# FM375_TEST_BOARD.net
KiCad netlist of a schematic drawn in Altium Designer
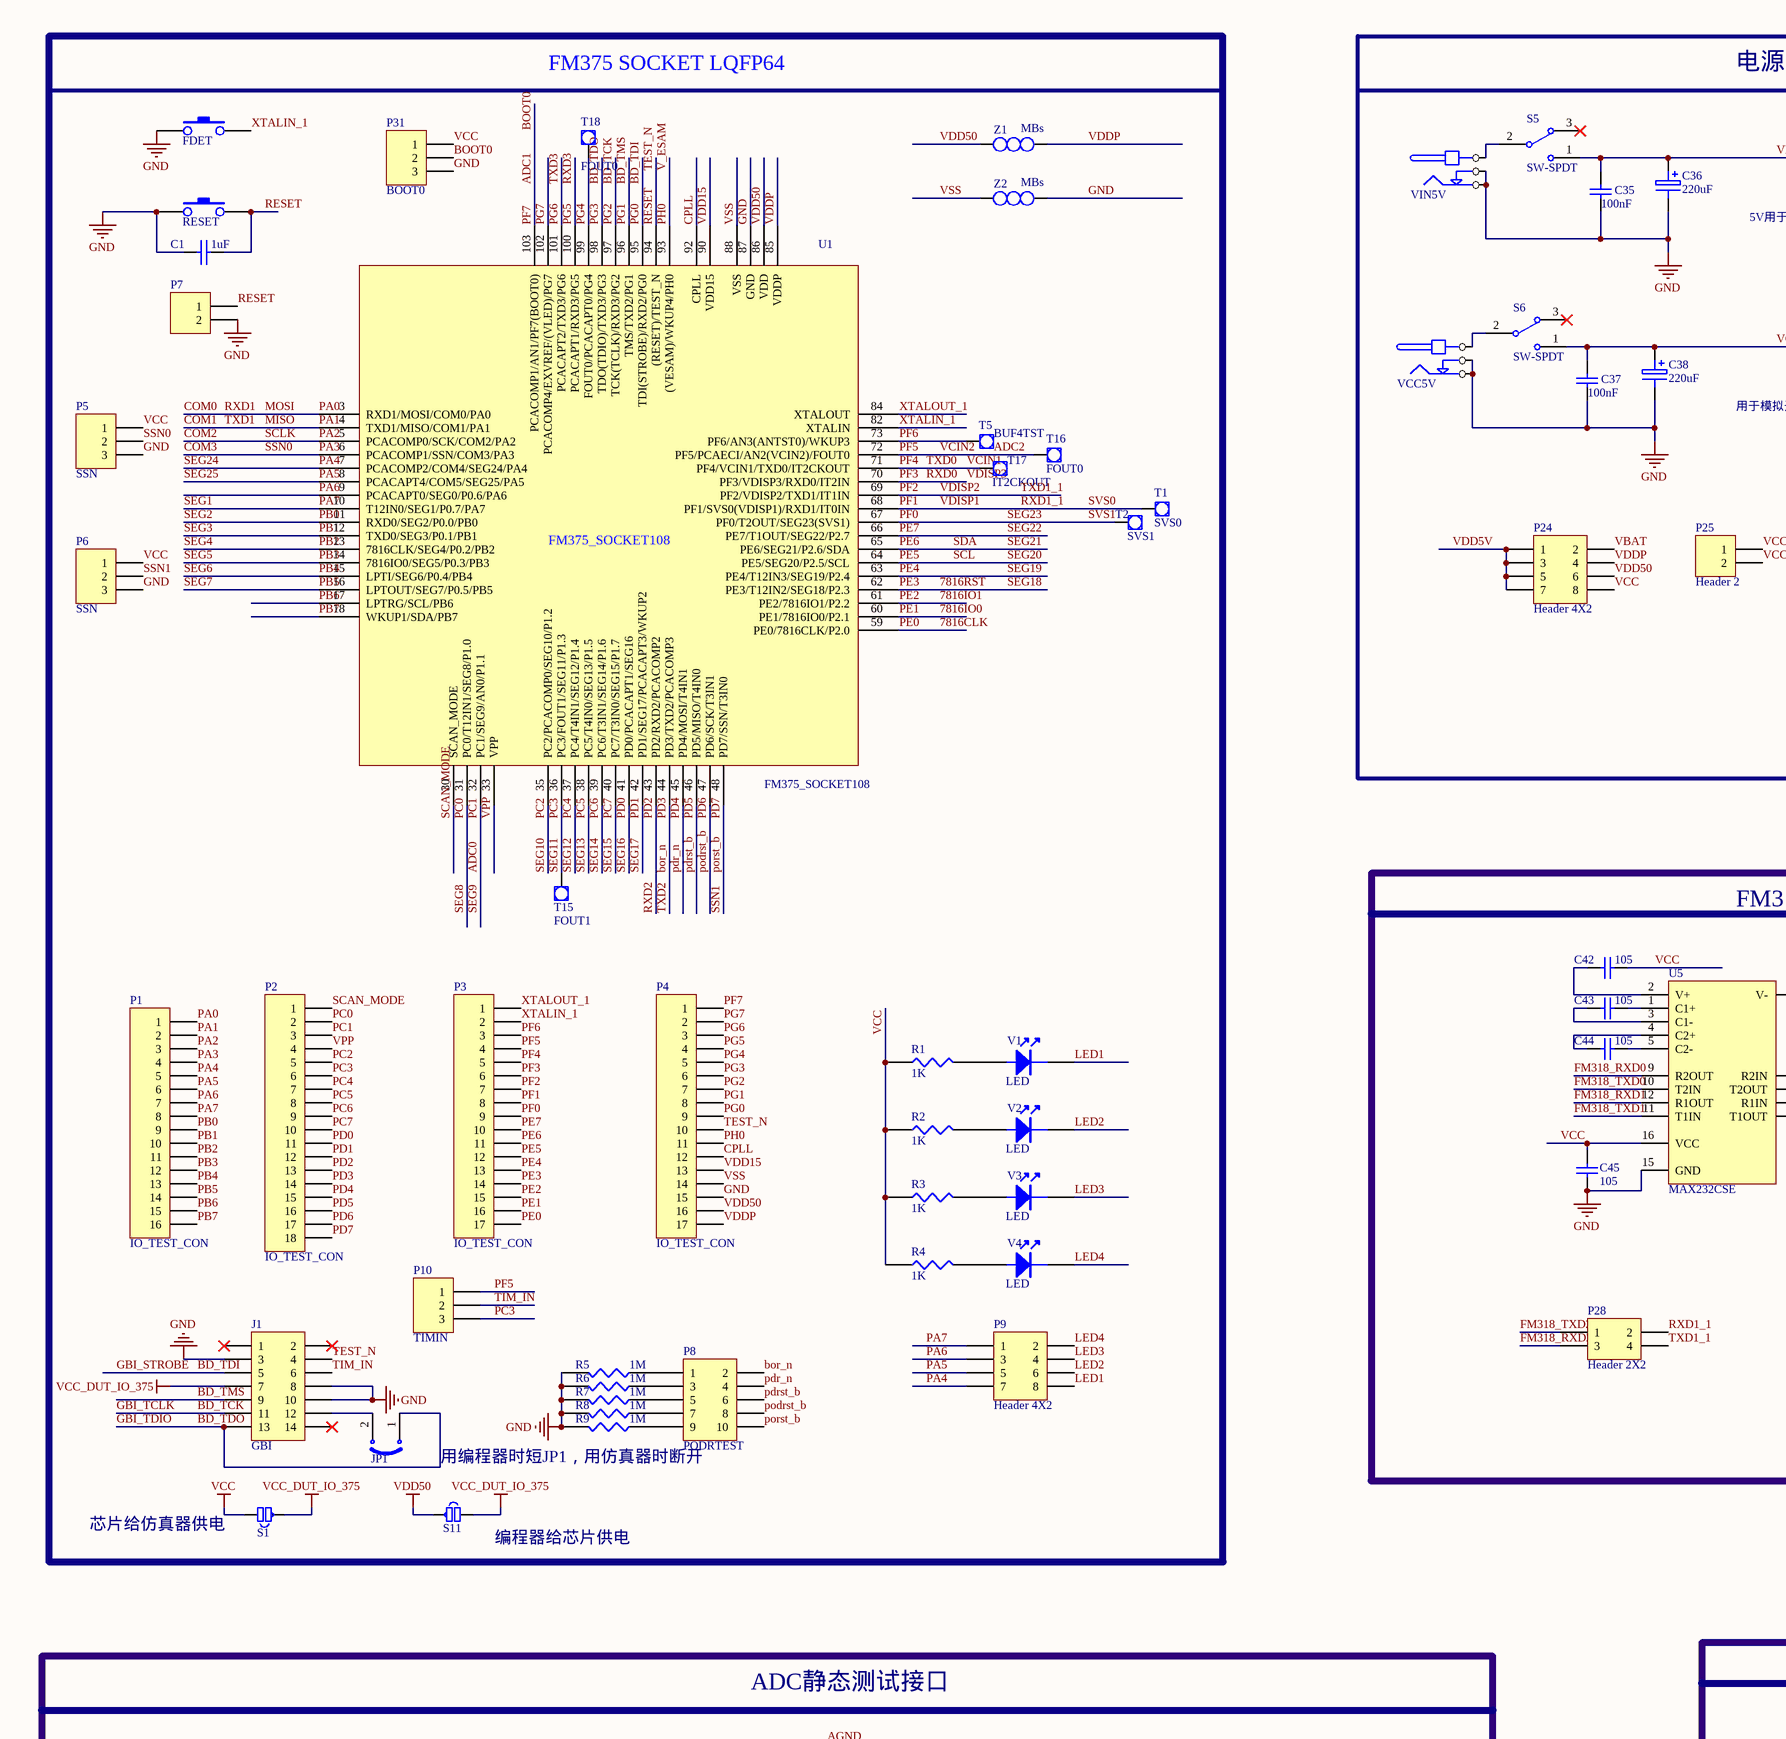
[diagram p0: FM375_TEST_BOARD.SchDoc, top left]
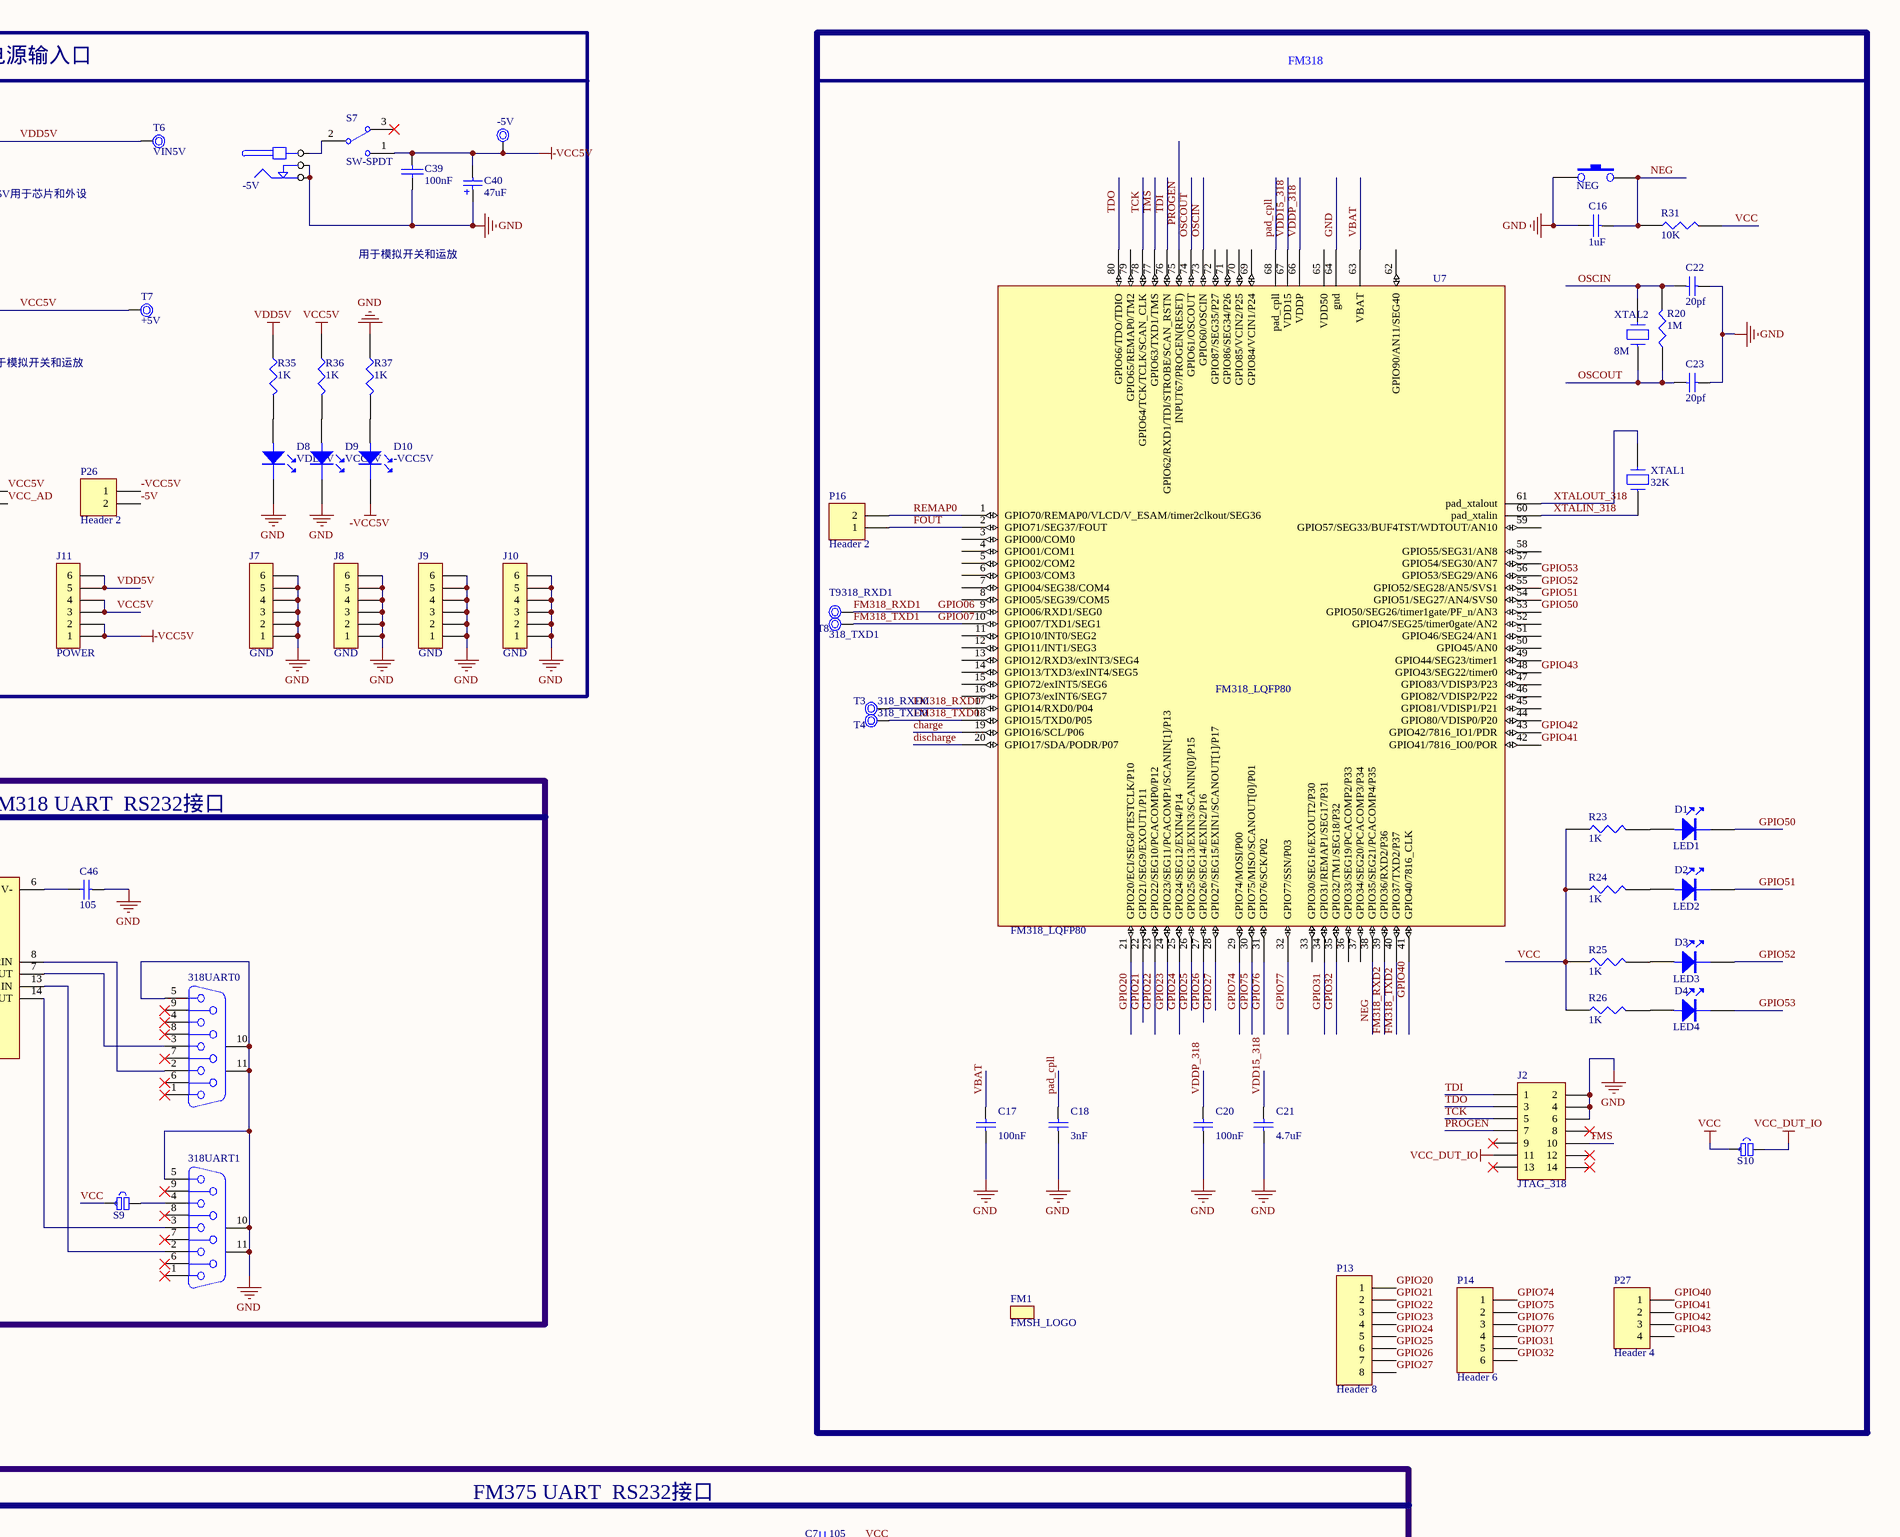
[diagram p1: FM375_TEST_BOARD.SchDoc, top right]
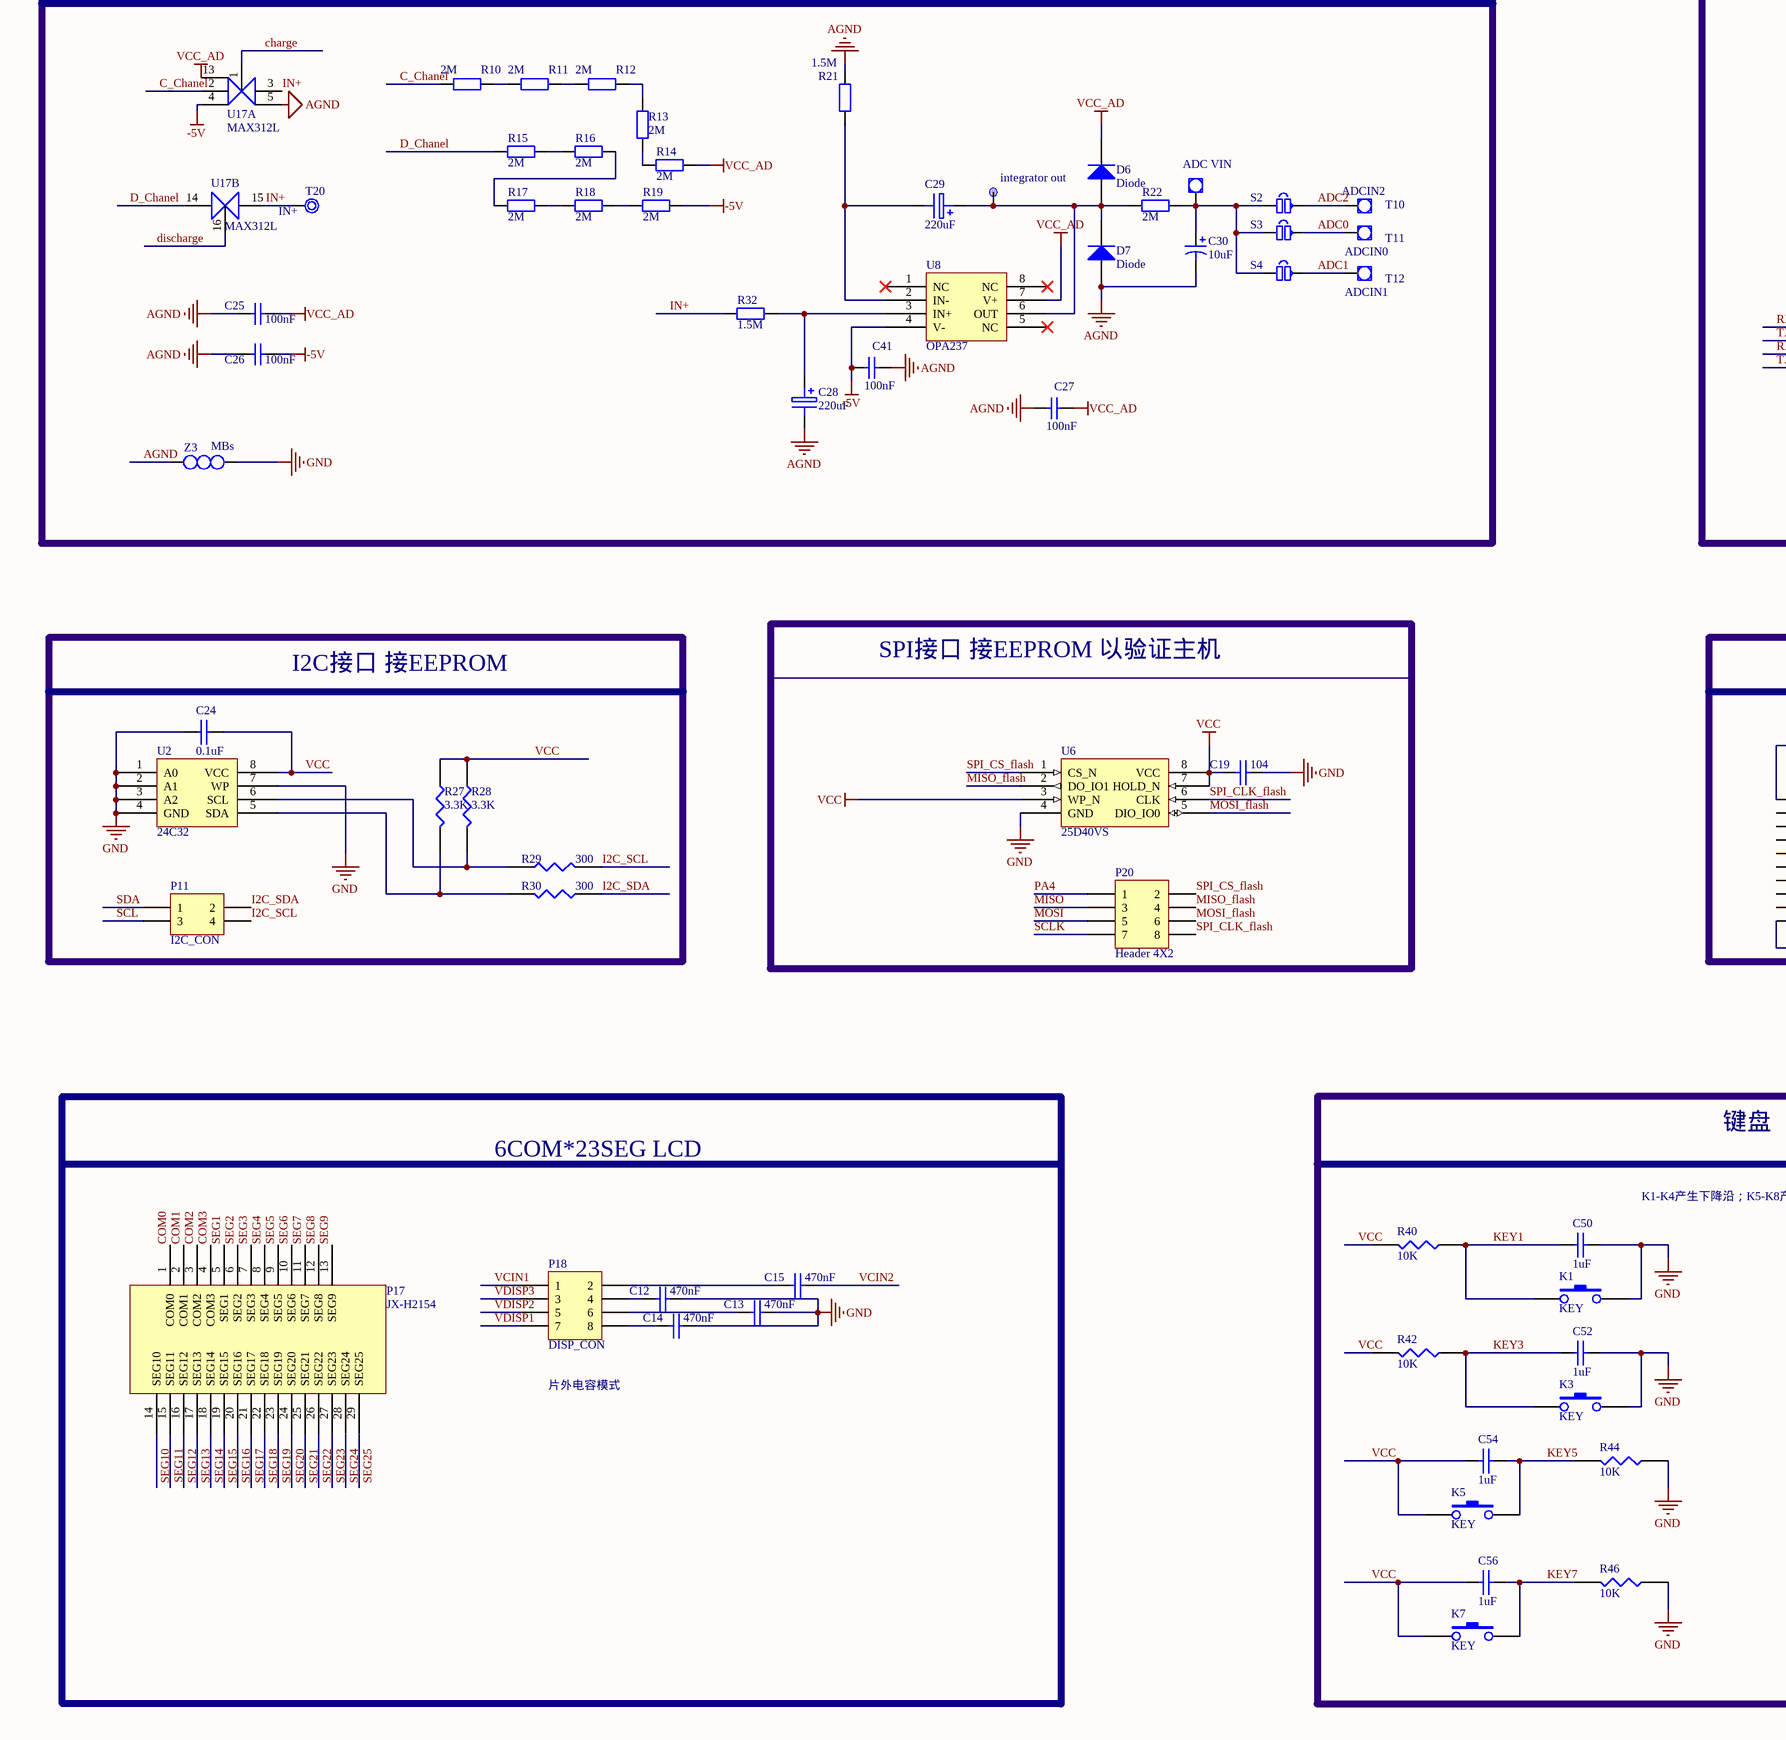
[diagram p2: FM375_TEST_BOARD.SchDoc, bottom left]
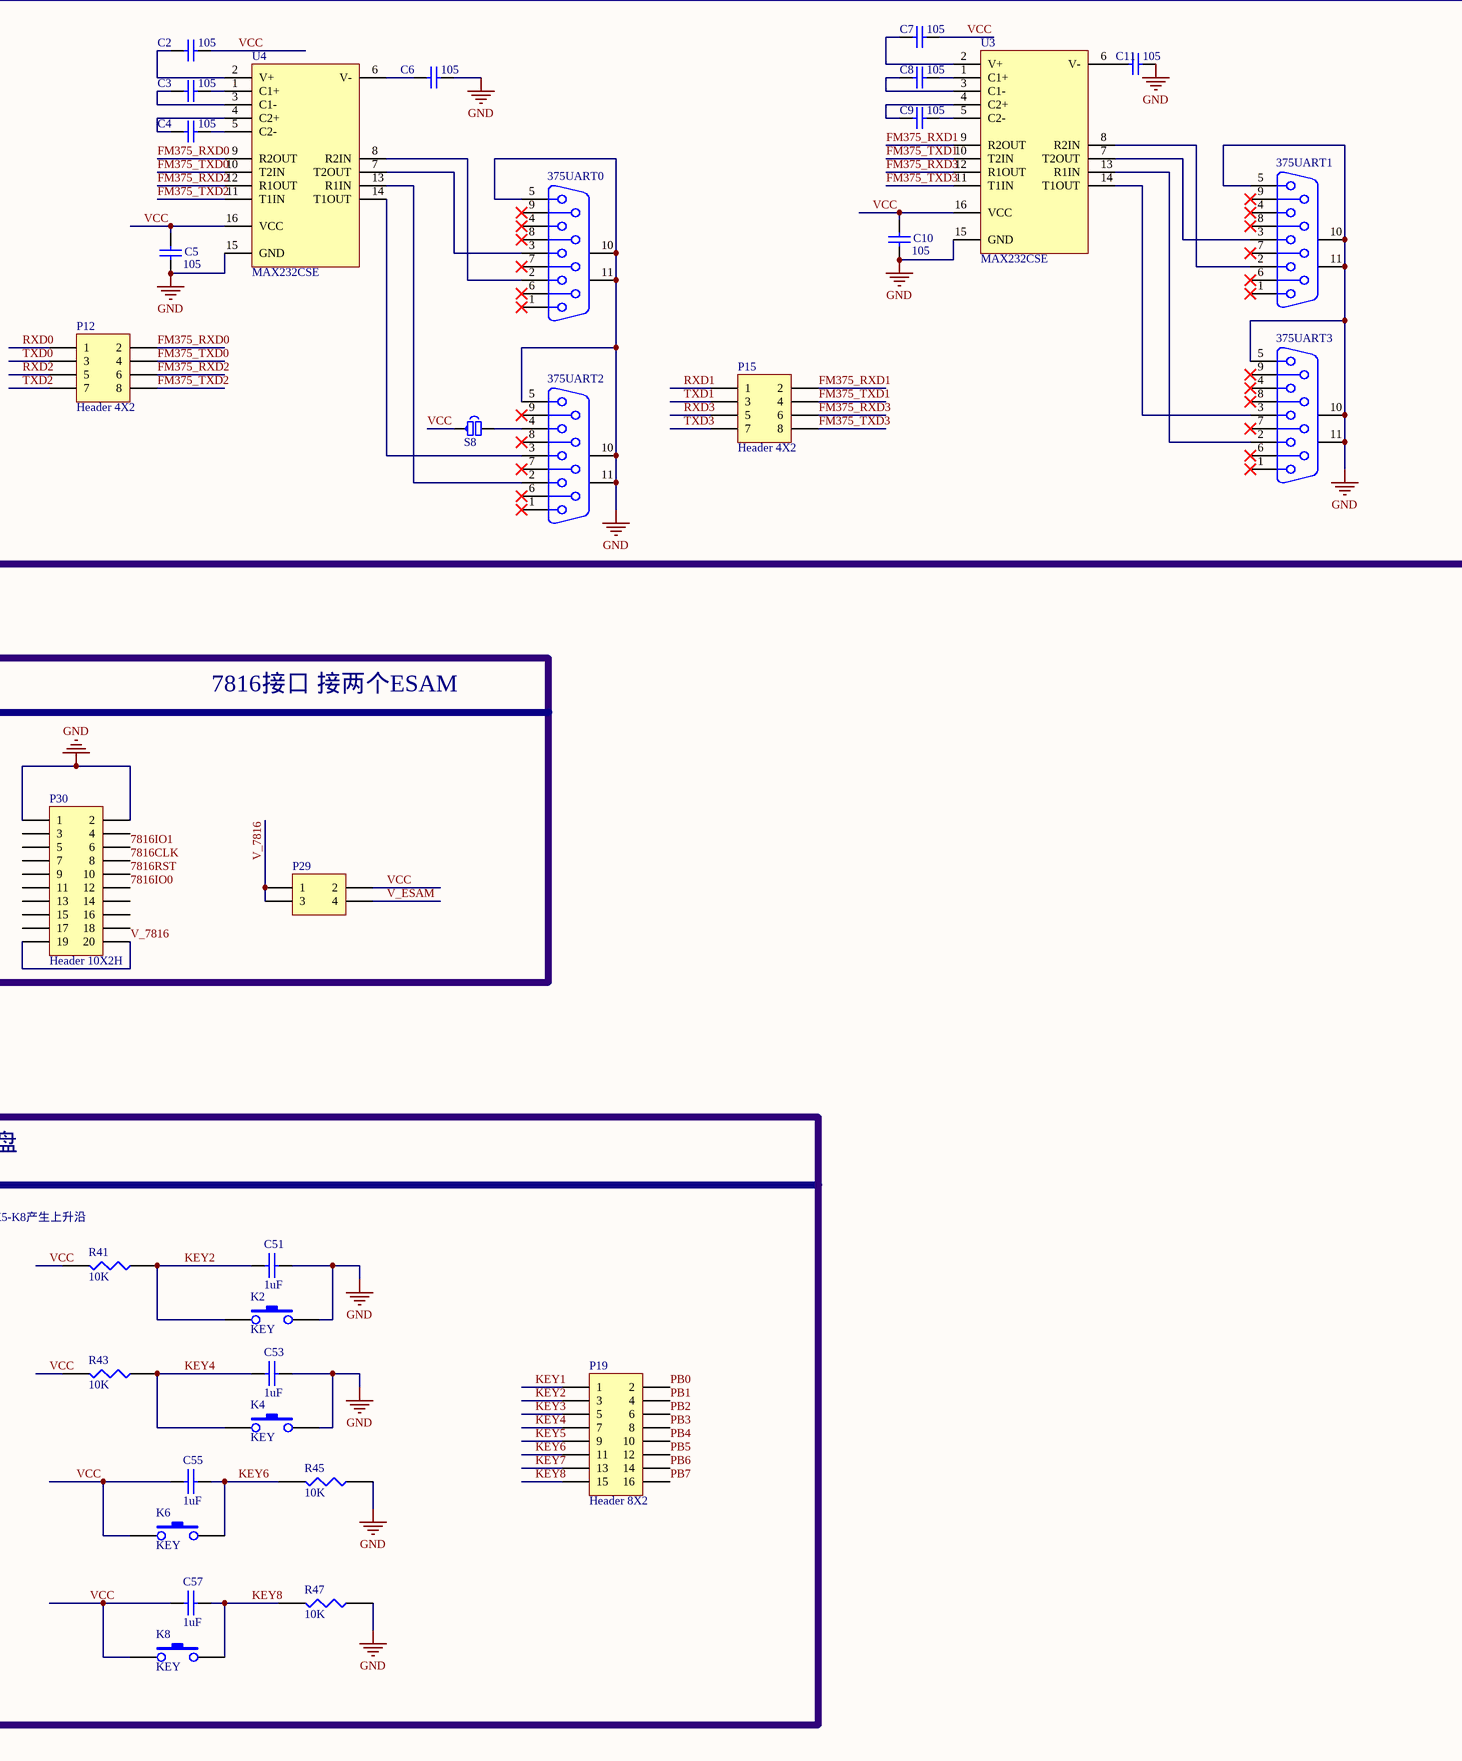
[diagram p3: FM375_TEST_BOARD.SchDoc, bottom right]

(export (version "E")
  (design (tool "Eeschema 10.0.6"))
  (components
    (comp (ref "-5V")
      (value "-5V")
      (footprint "TEST_PT")
      (libsource (lib "FM301_Verification") (part "TEST_POINT"))
    )
    (comp (ref "318UART0")
      (value "D Connector 9")
      (footprint "DB9RA/M")
      (description "Receptacle Assembly, 9 Position, Right Angle")
      (fields (field (name "PUBLISHER") "Altium Limited"))
      (libsource (lib "Miscellaneous Connectors") (part "D Connector 9"))
    )
    (comp (ref "318UART1")
      (value "D Connector 9")
      (footprint "DB9RA/M")
      (description "Receptacle Assembly, 9 Position, Right Angle")
      (fields (field (name "PUBLISHER") "Altium Limited"))
      (libsource (lib "Miscellaneous Connectors") (part "D Connector 9"))
    )
    (comp (ref "375UART0")
      (value "D Connector 9")
      (footprint "DB9RA/M")
      (description "Receptacle Assembly, 9 Position, Right Angle")
      (fields (field (name "PUBLISHER") "Altium Limited"))
      (libsource (lib "Miscellaneous Connectors") (part "D Connector 9"))
    )
    (comp (ref "375UART1")
      (value "D Connector 9")
      (footprint "DB9RA/M")
      (description "Receptacle Assembly, 9 Position, Right Angle")
      (fields (field (name "PUBLISHER") "Altium Limited"))
      (libsource (lib "Miscellaneous Connectors") (part "D Connector 9"))
    )
    (comp (ref "375UART2")
      (value "D Connector 9")
      (footprint "DB9RA/M")
      (description "Receptacle Assembly, 9 Position, Right Angle")
      (fields (field (name "PUBLISHER") "Altium Limited"))
      (libsource (lib "Miscellaneous Connectors") (part "D Connector 9"))
    )
    (comp (ref "375UART3")
      (value "D Connector 9")
      (footprint "DB9RA/M")
      (description "Receptacle Assembly, 9 Position, Right Angle")
      (fields (field (name "PUBLISHER") "Altium Limited"))
      (libsource (lib "Miscellaneous Connectors") (part "D Connector 9"))
    )
    (comp (ref "ADC VIN")
      (value "ADCIN2")
      (footprint "SIP1")
      (libsource (lib "FM301_TEST") (part "TEST_POINT2"))
    )
    (comp (ref "C1")
      (value "1uF")
      (footprint "0805")
      (description "一般瓷片电容、直插选用RAD0.1，贴片选用0805")
      (libsource (lib "FM_SCH") (part "CAP"))
    )
    (comp (ref "C2") (value "105") (footprint "0805") (libsource (lib "常用器件库_SCH") (part "CAP")))
    (comp (ref "C3") (value "105") (footprint "0805") (libsource (lib "常用器件库_SCH") (part "CAP")))
    (comp (ref "C4") (value "105") (footprint "0805") (libsource (lib "常用器件库_SCH") (part "CAP")))
    (comp (ref "C5") (value "105") (footprint "0805") (libsource (lib "常用器件库_SCH") (part "CAP")))
    (comp (ref "C6") (value "105") (footprint "0805") (libsource (lib "常用器件库_SCH") (part "CAP")))
    (comp (ref "C7") (value "105") (footprint "0805") (libsource (lib "常用器件库_SCH") (part "CAP")))
    (comp (ref "C8") (value "105") (footprint "0805") (libsource (lib "常用器件库_SCH") (part "CAP")))
    (comp (ref "C9") (value "105") (footprint "0805") (libsource (lib "常用器件库_SCH") (part "CAP")))
    (comp (ref "C10") (value "105") (footprint "0805") (libsource (lib "常用器件库_SCH") (part "CAP")))
    (comp (ref "C11") (value "105") (footprint "0805") (libsource (lib "常用器件库_SCH") (part "CAP")))
    (comp (ref "C12")
      (value "470nF")
      (footprint "0805")
      (description "Capacitor")
      (libsource (lib "*") (part "CAP"))
    )
    (comp (ref "C13")
      (value "470nF")
      (footprint "0805")
      (description "Capacitor")
      (libsource (lib "*") (part "CAP"))
    )
    (comp (ref "C14")
      (value "470nF")
      (footprint "0805")
      (description "Capacitor")
      (libsource (lib "*") (part "CAP"))
    )
    (comp (ref "C15")
      (value "470nF")
      (footprint "0805")
      (description "Capacitor")
      (libsource (lib "*") (part "CAP"))
    )
    (comp (ref "C16")
      (value "1uF")
      (footprint "0805")
      (description "一般瓷片电容、直插选用RAD0.1，贴片选用0805")
      (libsource (lib "FM_SCH") (part "CAP"))
    )
    (comp (ref "C17")
      (value "100nF")
      (footprint "0805")
      (description "Capacitor")
      (fields (field (name "Comment") "104") (field (name "PUBLISHER") "Altium Limited"))
      (libsource (lib "Miscellaneous Devices") (part "104"))
    )
    (comp (ref "C18")
      (value "3nF")
      (footprint "0805")
      (description "Capacitor")
      (fields (field (name "Comment") "104") (field (name "PUBLISHER") "Altium Limited"))
      (libsource (lib "Miscellaneous Devices") (part "104"))
    )
    (comp (ref "C19")
      (value "104")
      (footprint "0805")
      (description "一般瓷片电容、直插选用RAD0.1，贴片选用0805")
      (libsource (lib "FM_SCH") (part "CAP"))
    )
    (comp (ref "C20")
      (value "100nF")
      (footprint "0805")
      (description "Capacitor")
      (fields (field (name "Comment") "104") (field (name "PUBLISHER") "Altium Limited"))
      (libsource (lib "Miscellaneous Devices") (part "Cap"))
    )
    (comp (ref "C21")
      (value "4.7uF")
      (footprint "0805")
      (description "Capacitor")
      (fields (field (name "Comment") "4.7uf") (field (name "PUBLISHER") "Altium Limited"))
      (libsource (lib "Miscellaneous Devices") (part "Cap"))
    )
    (comp (ref "C22")
      (value "20pf")
      (footprint "0805")
      (description "Capacitor")
      (fields (field (name "PUBLISHER") "Altium Limited"))
      (libsource (lib "Miscellaneous Devices") (part "Cap"))
    )
    (comp (ref "C23")
      (value "20pf")
      (footprint "0805")
      (description "Capacitor")
      (fields (field (name "PUBLISHER") "Altium Limited"))
      (libsource (lib "Miscellaneous Devices") (part "Cap"))
    )
    (comp (ref "C24")
      (value "0.1uF")
      (footprint "0805")
      (description "Capacitor")
      (libsource (lib "*") (part "CAP"))
    )
    (comp (ref "C25")
      (value "100nF")
      (footprint "0805")
      (description "Capacitor")
      (fields (field (name "PUBLISHER") "Altium Limited"))
      (libsource (lib "Miscellaneous Devices") (part "CAP"))
    )
    (comp (ref "C26")
      (value "100nF")
      (footprint "0805")
      (description "Capacitor")
      (fields (field (name "PUBLISHER") "Altium Limited"))
      (libsource (lib "Miscellaneous Devices") (part "CAP"))
    )
    (comp (ref "C27")
      (value "100nF")
      (footprint "0805")
      (description "Capacitor")
      (fields (field (name "PUBLISHER") "Altium Limited"))
      (libsource (lib "Miscellaneous Devices") (part "CAP"))
    )
    (comp (ref "C28") (value "220uF") (footprint "NSM-EC") (libsource (lib "*") (part "ELECTRO1")))
    (comp (ref "C29") (value "220uF") (footprint "NSM-EC") (libsource (lib "*") (part "ELECTRO1")))
    (comp (ref "C30")
      (value "10uF")
      (footprint "SMD电容_B型_1")
      (description "Polarized Capacitor (Radial)")
      (fields (field (name "PUBLISHER") "Altium Limited"))
      (libsource (lib "Miscellaneous Devices") (part "Cap Pol1"))
    )
    (comp (ref "C35")
      (value "100nF")
      (footprint "0805")
      (description "Capacitor")
      (fields (field (name "PUBLISHER") "Altium Limited"))
      (libsource (lib "Miscellaneous Devices") (part "CAP"))
    )
    (comp (ref "C36") (value "220uF") (footprint "NSM-EC") (libsource (lib "*") (part "ELECTRO1")))
    (comp (ref "C37")
      (value "100nF")
      (footprint "0805")
      (description "Capacitor")
      (fields (field (name "PUBLISHER") "Altium Limited"))
      (libsource (lib "Miscellaneous Devices") (part "CAP"))
    )
    (comp (ref "C38") (value "220uF") (footprint "NSM-EC") (libsource (lib "*") (part "ELECTRO1")))
    (comp (ref "C39")
      (value "100nF")
      (footprint "0805")
      (description "一般瓷片电容、直插选用RAD0.1，贴片选用0805")
      (libsource (lib "FM_SCH") (part "CAP"))
    )
    (comp (ref "C40")
      (value "47uF")
      (footprint "SMD电容_B型_1")
      (description "Polarized Capacitor (Axial)")
      (fields (field (name "PUBLISHER") "Altium Limited"))
      (libsource (lib "Miscellaneous Devices") (part "Cap Pol2"))
    )
    (comp (ref "C41")
      (value "100nF")
      (footprint "0805")
      (description "Capacitor")
      (fields (field (name "PUBLISHER") "Altium Limited"))
      (libsource (lib "Miscellaneous Devices") (part "CAP"))
    )
    (comp (ref "C42") (value "105") (footprint "0805") (libsource (lib "常用器件库_SCH") (part "CAP")))
    (comp (ref "C43") (value "105") (footprint "0805") (libsource (lib "常用器件库_SCH") (part "CAP")))
    (comp (ref "C44") (value "105") (footprint "0805") (libsource (lib "常用器件库_SCH") (part "CAP")))
    (comp (ref "C45") (value "105") (footprint "0805") (libsource (lib "常用器件库_SCH") (part "CAP")))
    (comp (ref "C46") (value "105") (footprint "0805") (libsource (lib "常用器件库_SCH") (part "CAP")))
    (comp (ref "C50")
      (value "1uF")
      (footprint "0805")
      (description "Capacitor")
      (libsource (lib "*") (part "CAP"))
    )
    (comp (ref "C51")
      (value "1uF")
      (footprint "0805")
      (description "Capacitor")
      (libsource (lib "*") (part "CAP"))
    )
    (comp (ref "C52")
      (value "1uF")
      (footprint "0805")
      (description "Capacitor")
      (libsource (lib "*") (part "CAP"))
    )
    (comp (ref "C53")
      (value "1uF")
      (footprint "0805")
      (description "Capacitor")
      (libsource (lib "*") (part "CAP"))
    )
    (comp (ref "C54")
      (value "1uF")
      (footprint "0805")
      (description "Capacitor")
      (libsource (lib "*") (part "CAP"))
    )
    (comp (ref "C55")
      (value "1uF")
      (footprint "0805")
      (description "Capacitor")
      (libsource (lib "*") (part "CAP"))
    )
    (comp (ref "C56")
      (value "1uF")
      (footprint "0805")
      (description "Capacitor")
      (libsource (lib "*") (part "CAP"))
    )
    (comp (ref "C57")
      (value "1uF")
      (footprint "0805")
      (description "Capacitor")
      (libsource (lib "*") (part "CAP"))
    )
    (comp (ref "D1") (value "LED1") (footprint "LED-DIODE0.1-BIGHOLE") (libsource (lib "*") (part "LED")))
    (comp (ref "D2") (value "LED2") (footprint "LED-DIODE0.1-BIGHOLE") (libsource (lib "*") (part "LED")))
    (comp (ref "D3") (value "LED3") (footprint "LED-DIODE0.1-BIGHOLE") (libsource (lib "*") (part "LED")))
    (comp (ref "D4") (value "LED4") (footprint "LED-DIODE0.1-BIGHOLE") (libsource (lib "*") (part "LED")))
    (comp (ref "D6")
      (value "Diode")
      (footprint "DIODE_M7")
      (description "Default Diode")
      (fields (field (name "PUBLISHER") "Altium Limited"))
      (libsource (lib "Miscellaneous Devices") (part "Diode"))
    )
    (comp (ref "D7")
      (value "Diode")
      (footprint "DIODE_M7")
      (description "Default Diode")
      (fields (field (name "PUBLISHER") "Altium Limited"))
      (libsource (lib "Miscellaneous Devices") (part "Diode"))
    )
    (comp (ref "D8") (value "VDD5V") (footprint "LED-DIODE0.1-BIGHOLE") (libsource (lib "*") (part "LED")))
    (comp (ref "D9") (value "VCC5V") (footprint "LED-DIODE0.1-BIGHOLE") (libsource (lib "*") (part "LED")))
    (comp (ref "D10") (value "-VCC5V") (footprint "LED-DIODE0.1-BIGHOLE") (libsource (lib "*") (part "LED")))
    (comp (ref "FDET")
      (value "KEY")
      (footprint "BUTTON-S")
      (description "乒乓球按键（压下后接通，松开自动断开），较大按键尺寸12mmX12mm选用BUTTON-L封装，较小尺寸6mmX6mm选用BUTTON-S封装")
      (libsource (lib "*") (part "SW-PB"))
    )
    (comp (ref "FM1")
      (value "FMSH_LOGO")
      (footprint "FMSH-LOGO-1")
      (libsource (lib "FM296") (part "FMSH_LOGO"))
    )
    (comp (ref "integrator out") (value "MCO") (footprint "TEST_PT") (libsource (lib "MB672") (part "TP")))
    (comp (ref "J1")
      (value "GBI")
      (footprint "HDR7X2-LP")
      (description "Header, 7-Pin, Dual row")
      (fields (field (name "PUBLISHER") "Altium Limited"))
      (libsource (lib "Miscellaneous Connectors") (part "Header 7X2"))
    )
    (comp (ref "J2")
      (value "JTAG_318")
      (footprint "JTAG_BIRD")
      (description "Header, 7-Pin, Dual row")
      (fields (field (name "PUBLISHER") "Altium Limited"))
      (libsource (lib "Miscellaneous Connectors") (part "Header 7X2"))
    )
    (comp (ref "J7")
      (value "GND")
      (footprint "SIP6")
      (description "6pin的连接器，一般直插封装选用SIP6（间距2.54mm）")
      (libsource (lib "talentSCH1") (part "CON6"))
    )
    (comp (ref "J8")
      (value "GND")
      (footprint "SIP6")
      (description "6pin的连接器，一般直插封装选用SIP6（间距2.54mm）")
      (libsource (lib "talentSCH1") (part "CON6"))
    )
    (comp (ref "J9")
      (value "GND")
      (footprint "SIP6")
      (description "6pin的连接器，一般直插封装选用SIP6（间距2.54mm）")
      (libsource (lib "talentSCH1") (part "CON6"))
    )
    (comp (ref "J10")
      (value "GND")
      (footprint "SIP6")
      (description "6pin的连接器，一般直插封装选用SIP6（间距2.54mm）")
      (libsource (lib "talentSCH1") (part "CON6"))
    )
    (comp (ref "J11")
      (value "POWER")
      (footprint "SIP6")
      (description "6pin的连接器，一般直插封装选用SIP6（间距2.54mm）")
      (libsource (lib "talentSCH1") (part "CON6"))
    )
    (comp (ref "JP1")
      (value "~")
      (footprint "SIP2")
      (description "Jumper")
      (libsource (lib "FM301_TEST") (part "JUMPER"))
    )
    (comp (ref "K1")
      (value "KEY")
      (footprint "BUTTON-S")
      (description "乒乓球按键（压下后接通，松开自动断开），较大按键尺寸12mmX12mm选用BUTTON-L封装，较小尺寸6mmX6mm选用BUTTON-S封装")
      (libsource (lib "*") (part "SW-PB"))
    )
    (comp (ref "K2")
      (value "KEY")
      (footprint "BUTTON-S")
      (description "乒乓球按键（压下后接通，松开自动断开），较大按键尺寸12mmX12mm选用BUTTON-L封装，较小尺寸6mmX6mm选用BUTTON-S封装")
      (libsource (lib "*") (part "SW-PB"))
    )
    (comp (ref "K3")
      (value "KEY")
      (footprint "BUTTON-S")
      (description "乒乓球按键（压下后接通，松开自动断开），较大按键尺寸12mmX12mm选用BUTTON-L封装，较小尺寸6mmX6mm选用BUTTON-S封装")
      (libsource (lib "*") (part "SW-PB"))
    )
    (comp (ref "K4")
      (value "KEY")
      (footprint "BUTTON-S")
      (description "乒乓球按键（压下后接通，松开自动断开），较大按键尺寸12mmX12mm选用BUTTON-L封装，较小尺寸6mmX6mm选用BUTTON-S封装")
      (libsource (lib "*") (part "SW-PB"))
    )
    (comp (ref "K5")
      (value "KEY")
      (footprint "BUTTON-S")
      (description "乒乓球按键（压下后接通，松开自动断开），较大按键尺寸12mmX12mm选用BUTTON-L封装，较小尺寸6mmX6mm选用BUTTON-S封装")
      (libsource (lib "*") (part "SW-PB"))
    )
    (comp (ref "K6")
      (value "KEY")
      (footprint "BUTTON-S")
      (description "乒乓球按键（压下后接通，松开自动断开），较大按键尺寸12mmX12mm选用BUTTON-L封装，较小尺寸6mmX6mm选用BUTTON-S封装")
      (libsource (lib "*") (part "SW-PB"))
    )
    (comp (ref "K7")
      (value "KEY")
      (footprint "BUTTON-S")
      (description "乒乓球按键（压下后接通，松开自动断开），较大按键尺寸12mmX12mm选用BUTTON-L封装，较小尺寸6mmX6mm选用BUTTON-S封装")
      (libsource (lib "*") (part "SW-PB"))
    )
    (comp (ref "K8")
      (value "KEY")
      (footprint "BUTTON-S")
      (description "乒乓球按键（压下后接通，松开自动断开），较大按键尺寸12mmX12mm选用BUTTON-L封装，较小尺寸6mmX6mm选用BUTTON-S封装")
      (libsource (lib "*") (part "SW-PB"))
    )
    (comp (ref "NEG")
      (value "KEY")
      (footprint "BUTTON-S")
      (description "乒乓球按键（压下后接通，松开自动断开），较大按键尺寸12mmX12mm选用BUTTON-L封装，较小尺寸6mmX6mm选用BUTTON-S封装")
      (libsource (lib "*") (part "SW-PB"))
    )
    (comp (ref "P1")
      (value "IO_TEST_CON")
      (footprint "HDR1X16")
      (description "Header, 16-Pin")
      (fields (field (name "PUBLISHER") "Altium Limited"))
      (libsource (lib "Miscellaneous Connectors") (part "Header 16"))
    )
    (comp (ref "P2")
      (value "IO_TEST_CON")
      (footprint "HDR1X18")
      (description "Header, 18-Pin")
      (fields (field (name "PUBLISHER") "Altium Limited"))
      (libsource (lib "Miscellaneous Connectors") (part "Header 18"))
    )
    (comp (ref "P3")
      (value "IO_TEST_CON")
      (footprint "HDR1X17")
      (description "Header, 17-Pin")
      (fields (field (name "PUBLISHER") "Altium Limited"))
      (libsource (lib "Miscellaneous Connectors") (part "Header 17"))
    )
    (comp (ref "P4")
      (value "IO_TEST_CON")
      (footprint "HDR1X17")
      (description "Header, 17-Pin")
      (fields (field (name "PUBLISHER") "Altium Limited"))
      (libsource (lib "Miscellaneous Connectors") (part "Header 17"))
    )
    (comp (ref "P5")
      (value "SSN")
      (footprint "HDR1X3")
      (description "Header, 3-Pin")
      (fields (field (name "PUBLISHER") "Altium Limited"))
      (libsource (lib "Miscellaneous Connectors") (part "Header 3"))
    )
    (comp (ref "P6")
      (value "SSN")
      (footprint "HDR1X3")
      (description "Header, 3-Pin")
      (fields (field (name "PUBLISHER") "Altium Limited"))
      (libsource (lib "Miscellaneous Connectors") (part "Header 3"))
    )
    (comp (ref "P7")
      (value "Header 2")
      (footprint "HDR1X2")
      (description "Header, 2-Pin")
      (fields (field (name "PUBLISHER") "Altium Limited"))
      (libsource (lib "Miscellaneous Connectors") (part "Header 2"))
    )
    (comp (ref "P8")
      (value "PODRTEST")
      (footprint "HDR2X5")
      (description "Header, 5-Pin, Dual row")
      (fields (field (name "PUBLISHER") "Altium Limited"))
      (libsource (lib "Miscellaneous Connectors") (part "Header 5X2"))
    )
    (comp (ref "P9")
      (value "Header 4X2")
      (footprint "HDR2X4")
      (description "Header, 4-Pin, Dual row")
      (fields (field (name "PUBLISHER") "Altium Limited"))
      (libsource (lib "Miscellaneous Connectors") (part "Header 4X2"))
    )
    (comp (ref "P10")
      (value "TIMIN")
      (footprint "HDR1X3")
      (description "Header, 3-Pin")
      (fields (field (name "PUBLISHER") "Altium Limited"))
      (libsource (lib "Miscellaneous Connectors") (part "Header 3"))
    )
    (comp (ref "P11")
      (value "I2C_CON")
      (footprint "HDR2X2")
      (description "Header, 2-Pin, Dual row")
      (fields (field (name "PUBLISHER") "Altium Limited"))
      (libsource (lib "Miscellaneous Connectors") (part "Header 2X2"))
    )
    (comp (ref "P12")
      (value "Header 4X2")
      (footprint "HDR2X4")
      (description "Header, 4-Pin, Dual row")
      (fields (field (name "PUBLISHER") "Altium Limited"))
      (libsource (lib "Miscellaneous Connectors") (part "Header 4X2"))
    )
    (comp (ref "P13")
      (value "Header 8")
      (footprint "HDR1X8")
      (description "Header, 8-Pin")
      (fields (field (name "PUBLISHER") "Altium Limited"))
      (libsource (lib "Miscellaneous Connectors") (part "Header 8"))
    )
    (comp (ref "P14")
      (value "Header 6")
      (footprint "HDR1X6")
      (description "Header, 6-Pin")
      (fields (field (name "PUBLISHER") "Altium Limited"))
      (libsource (lib "Miscellaneous Connectors") (part "Header 6"))
    )
    (comp (ref "P15")
      (value "Header 4X2")
      (footprint "HDR2X4")
      (description "Header, 4-Pin, Dual row")
      (fields (field (name "PUBLISHER") "Altium Limited"))
      (libsource (lib "Miscellaneous Connectors") (part "Header 4X2"))
    )
    (comp (ref "P16")
      (value "Header 2")
      (footprint "HDR1X2")
      (description "Header, 2-Pin")
      (fields (field (name "PUBLISHER") "Altium Limited"))
      (libsource (lib "") (part "Header 2_1"))
    )
    (comp (ref "P17")
      (value "JX-H2154")
      (footprint "JX-H2154")
      (libsource (lib "FM340_TEST") (part "LCD_JX-H2154"))
    )
    (comp (ref "P18")
      (value "DISP_CON")
      (footprint "HDR2X4")
      (description "Header, 4-Pin, Dual row")
      (fields (field (name "PUBLISHER") "Altium Limited"))
      (libsource (lib "Miscellaneous Connectors") (part "Header 4X2"))
    )
    (comp (ref "P19")
      (value "Header 8X2")
      (footprint "HDR2X8")
      (description "Header, 8-Pin, Dual row")
      (fields (field (name "PUBLISHER") "Altium Limited"))
      (libsource (lib "Miscellaneous Connectors") (part "Header 8X2"))
    )
    (comp (ref "P20")
      (value "Header 4X2")
      (footprint "HDR2X4")
      (description "Header, 4-Pin, Dual row")
      (fields (field (name "PUBLISHER") "Altium Limited"))
      (libsource (lib "Miscellaneous Connectors") (part "Header 4X2"))
    )
    (comp (ref "P21") (value "VIN5V") (footprint "POWERJACK") (libsource (lib "插座") (part "9VPOWER")))
    (comp (ref "P22") (value "VCC5V") (footprint "POWERJACK") (libsource (lib "插座") (part "9VPOWER")))
    (comp (ref "P23") (value "-5V") (footprint "POWERJACK") (libsource (lib "插座") (part "9VPOWER")))
    (comp (ref "P24")
      (value "Header 4X2")
      (footprint "HDR2X4")
      (description "Header, 4-Pin, Dual row")
      (fields (field (name "PUBLISHER") "Altium Limited"))
      (libsource (lib "Miscellaneous Connectors") (part "Header 4X2"))
    )
    (comp (ref "P25")
      (value "Header 2")
      (footprint "HDR1X2")
      (description "Header, 2-Pin")
      (fields (field (name "PUBLISHER") "Altium Limited"))
      (libsource (lib "Miscellaneous Connectors") (part "Header 2"))
    )
    (comp (ref "P26")
      (value "Header 2")
      (footprint "HDR1X2")
      (description "Header, 2-Pin")
      (fields (field (name "PUBLISHER") "Altium Limited"))
      (libsource (lib "Miscellaneous Connectors") (part "Header 2"))
    )
    (comp (ref "P27")
      (value "Header 4")
      (footprint "HDR1X4")
      (description "Header, 4-Pin")
      (fields (field (name "PUBLISHER") "Altium Limited"))
      (libsource (lib "Miscellaneous Connectors") (part "Header 4"))
    )
    (comp (ref "P28")
      (value "Header 2X2")
      (footprint "HDR2X2")
      (description "Header, 2-Pin, Dual row")
      (fields (field (name "PUBLISHER") "Altium Limited"))
      (libsource (lib "Miscellaneous Connectors") (part "Header 2X2"))
    )
    (comp (ref "P29")
      (value "Header 2X2")
      (footprint "HDR2X2")
      (description "Header, 2-Pin, Dual row")
      (fields (field (name "PUBLISHER") "Altium Limited"))
      (libsource (lib "Miscellaneous Connectors") (part "Header 2X2"))
    )
    (comp (ref "P30")
      (value "Header 10X2H")
      (footprint "HDR2X10H")
      (description "Header, 10-Pin, Dual row, Right Angle")
      (fields (field (name "PUBLISHER") "Altium Limited"))
      (libsource (lib "Miscellaneous Connectors") (part "Header 10X2H"))
    )
    (comp (ref "P31")
      (value "BOOT0")
      (footprint "HDR1X3")
      (description "Header, 3-Pin")
      (fields (field (name "PUBLISHER") "Altium Limited"))
      (libsource (lib "Miscellaneous Connectors") (part "Header 3"))
    )
    (comp (ref "R1")
      (value "1K")
      (footprint "0805")
      (description "电阻，1/4w的金属膜直插可选AXIAL0.4封装（长度10mm），贴片可选0805封装，其他电阻可选AXIAL0.5～AXIAL1.0")
      (libsource (lib "") (part "RES1_1"))
    )
    (comp (ref "R2")
      (value "1K")
      (footprint "0805")
      (description "电阻，1/4w的金属膜直插可选AXIAL0.4封装（长度10mm），贴片可选0805封装，其他电阻可选AXIAL0.5～AXIAL1.0")
      (libsource (lib "") (part "RES1_1"))
    )
    (comp (ref "R3")
      (value "1K")
      (footprint "0805")
      (description "电阻，1/4w的金属膜直插可选AXIAL0.4封装（长度10mm），贴片可选0805封装，其他电阻可选AXIAL0.5～AXIAL1.0")
      (libsource (lib "") (part "RES1_1"))
    )
    (comp (ref "R4")
      (value "1K")
      (footprint "0805")
      (description "电阻，1/4w的金属膜直插可选AXIAL0.4封装（长度10mm），贴片可选0805封装，其他电阻可选AXIAL0.5～AXIAL1.0")
      (libsource (lib "") (part "RES1_1"))
    )
    (comp (ref "R5") (value "1M") (footprint "0805") (libsource (lib "*") (part "RES1")))
    (comp (ref "R6") (value "1M") (footprint "0805") (libsource (lib "*") (part "RES1")))
    (comp (ref "R7") (value "1M") (footprint "0805") (libsource (lib "*") (part "RES1")))
    (comp (ref "R8") (value "1M") (footprint "0805") (libsource (lib "*") (part "RES1")))
    (comp (ref "R9") (value "1M") (footprint "0805") (libsource (lib "*") (part "RES1")))
    (comp (ref "R10")
      (value "2M")
      (footprint "0805")
      (description "Resistor")
      (fields (field (name "PUBLISHER") "Altium Limited"))
      (libsource (lib "Miscellaneous Devices") (part "Res2"))
    )
    (comp (ref "R11")
      (value "2M")
      (footprint "0805")
      (description "Resistor")
      (fields (field (name "PUBLISHER") "Altium Limited"))
      (libsource (lib "Miscellaneous Devices") (part "Res2"))
    )
    (comp (ref "R12")
      (value "2M")
      (footprint "0805")
      (description "Resistor")
      (fields (field (name "PUBLISHER") "Altium Limited"))
      (libsource (lib "Miscellaneous Devices") (part "Res2"))
    )
    (comp (ref "R13")
      (value "2M")
      (footprint "0805")
      (description "Resistor")
      (fields (field (name "PUBLISHER") "Altium Limited"))
      (libsource (lib "") (part "Res2_2"))
    )
    (comp (ref "R14")
      (value "2M")
      (footprint "0805")
      (description "Resistor")
      (fields (field (name "PUBLISHER") "Altium Limited"))
      (libsource (lib "") (part "Res2_1"))
    )
    (comp (ref "R15")
      (value "2M")
      (footprint "0805")
      (description "Resistor")
      (fields (field (name "PUBLISHER") "Altium Limited"))
      (libsource (lib "") (part "Res2_1"))
    )
    (comp (ref "R16")
      (value "2M")
      (footprint "0805")
      (description "Resistor")
      (fields (field (name "PUBLISHER") "Altium Limited"))
      (libsource (lib "") (part "Res2_1"))
    )
    (comp (ref "R17")
      (value "2M")
      (footprint "0805")
      (description "Resistor")
      (fields (field (name "PUBLISHER") "Altium Limited"))
      (libsource (lib "") (part "Res2_1"))
    )
    (comp (ref "R18")
      (value "2M")
      (footprint "0805")
      (description "Resistor")
      (fields (field (name "PUBLISHER") "Altium Limited"))
      (libsource (lib "") (part "Res2_1"))
    )
    (comp (ref "R19")
      (value "2M")
      (footprint "0805")
      (description "Resistor")
      (fields (field (name "PUBLISHER") "Altium Limited"))
      (libsource (lib "") (part "Res2_1"))
    )
    (comp (ref "R20") (value "1M") (footprint "0805") (libsource (lib "FM301_TEST") (part "RES1")))
    (comp (ref "R21")
      (value "1.5M")
      (footprint "0805")
      (description "Resistor")
      (fields (field (name "PUBLISHER") "Altium Limited"))
      (libsource (lib "") (part "Res2_3"))
    )
    (comp (ref "R22")
      (value "2M")
      (footprint "0805")
      (description "Resistor")
      (fields (field (name "PUBLISHER") "Altium Limited"))
      (libsource (lib "Miscellaneous Devices") (part "Res2"))
    )
    (comp (ref "R23")
      (value "1K")
      (footprint "0805")
      (description "电阻，1/4w的金属膜直插可选AXIAL0.4封装（长度10mm），贴片可选0805封装，其他电阻可选AXIAL0.5～AXIAL1.0")
      (libsource (lib "") (part "RES1_1"))
    )
    (comp (ref "R24")
      (value "1K")
      (footprint "0805")
      (description "电阻，1/4w的金属膜直插可选AXIAL0.4封装（长度10mm），贴片可选0805封装，其他电阻可选AXIAL0.5～AXIAL1.0")
      (libsource (lib "") (part "RES1_1"))
    )
    (comp (ref "R25")
      (value "1K")
      (footprint "0805")
      (description "电阻，1/4w的金属膜直插可选AXIAL0.4封装（长度10mm），贴片可选0805封装，其他电阻可选AXIAL0.5～AXIAL1.0")
      (libsource (lib "") (part "RES1_1"))
    )
    (comp (ref "R26")
      (value "1K")
      (footprint "0805")
      (description "电阻，1/4w的金属膜直插可选AXIAL0.4封装（长度10mm），贴片可选0805封装，其他电阻可选AXIAL0.5～AXIAL1.0")
      (libsource (lib "") (part "RES1_1"))
    )
    (comp (ref "R27") (value "3.3K") (footprint "0805") (libsource (lib "*") (part "RES1")))
    (comp (ref "R28") (value "3.3K") (footprint "0805") (libsource (lib "*") (part "RES1")))
    (comp (ref "R29") (value "300") (footprint "0805") (libsource (lib "*") (part "RES1")))
    (comp (ref "R30") (value "300") (footprint "0805") (libsource (lib "*") (part "RES1")))
    (comp (ref "R31") (value "10K") (footprint "0805") (libsource (lib "*") (part "RES1")))
    (comp (ref "R32")
      (value "1.5M")
      (footprint "0805")
      (description "Resistor")
      (fields (field (name "PUBLISHER") "Altium Limited"))
      (libsource (lib "Miscellaneous Devices") (part "Res2"))
    )
    (comp (ref "R35") (value "1K") (footprint "0805") (libsource (lib "*") (part "RES1")))
    (comp (ref "R36") (value "1K") (footprint "0805") (libsource (lib "*") (part "RES1")))
    (comp (ref "R37") (value "1K") (footprint "0805") (libsource (lib "*") (part "RES1")))
    (comp (ref "R40") (value "10K") (footprint "0805") (libsource (lib "*") (part "RES1")))
    (comp (ref "R41") (value "10K") (footprint "0805") (libsource (lib "*") (part "RES1")))
    (comp (ref "R42") (value "10K") (footprint "0805") (libsource (lib "*") (part "RES1")))
    (comp (ref "R43") (value "10K") (footprint "0805") (libsource (lib "*") (part "RES1")))
    (comp (ref "R44") (value "10K") (footprint "0805") (libsource (lib "*") (part "RES1")))
    (comp (ref "R45") (value "10K") (footprint "0805") (libsource (lib "*") (part "RES1")))
    (comp (ref "R46") (value "10K") (footprint "0805") (libsource (lib "*") (part "RES1")))
    (comp (ref "R47") (value "10K") (footprint "0805") (libsource (lib "*") (part "RES1")))
    (comp (ref "RESET")
      (value "KEY")
      (footprint "FM340_TEST_BOARD2:BUTTON-S")
      (description "乒乓球按键（压下后接通，松开自动断开），较大按键尺寸12mmX12mm选用BUTTON-L封装，较小尺寸6mmX6mm选用BUTTON-S封装")
      (libsource (lib "*") (part "SW-PB"))
    )
    (comp (ref "S1") (value "SHORT") (footprint "0603_SHORT_Y") (libsource (lib "YaoZhenSch") (part "SHORT")))
    (comp (ref "S2") (value "JUMPER") (footprint "0603_SHORT_Y") (libsource (lib "FM312-PRJ") (part "SHORT")))
    (comp (ref "S3") (value "JUMPER") (footprint "0603_SHORT_Y") (libsource (lib "FM312-PRJ") (part "SHORT")))
    (comp (ref "S4") (value "JUMPER") (footprint "0603_SHORT_Y") (libsource (lib "FM312-PRJ") (part "SHORT")))
    (comp (ref "S5")
      (value "SW-SPDT")
      (footprint "SW2")
      (description "SPDT Subminiature Toggle Switch, Right Angle Mounting, Vertical Actuation")
      (fields (field (name "PUBLISHER") "Altium Limited"))
      (libsource (lib "Miscellaneous Devices") (part "SW-SPDT"))
    )
    (comp (ref "S6")
      (value "SW-SPDT")
      (footprint "SW2")
      (description "SPDT Subminiature Toggle Switch, Right Angle Mounting, Vertical Actuation")
      (fields (field (name "PUBLISHER") "Altium Limited"))
      (libsource (lib "Miscellaneous Devices") (part "SW-SPDT"))
    )
    (comp (ref "S7")
      (value "SW-SPDT")
      (footprint "SW2")
      (description "SPDT Subminiature Toggle Switch, Right Angle Mounting, Vertical Actuation")
      (fields (field (name "PUBLISHER") "Altium Limited"))
      (libsource (lib "Miscellaneous Devices") (part "SW-SPDT"))
    )
    (comp (ref "S8")
      (value "JUMPER")
      (footprint "0603_SHORT_Y")
      (libsource (lib "YaoZhenSch") (part "SHORT"))
    )
    (comp (ref "S9")
      (value "JUMPER")
      (footprint "0603_SHORT_Y")
      (libsource (lib "YaoZhenSch") (part "SHORT"))
    )
    (comp (ref "S10")
      (value "SHORT")
      (footprint "0603_SHORT_Y")
      (libsource (lib "YaoZhenSch") (part "SHORT"))
    )
    (comp (ref "S11")
      (value "SHORT")
      (footprint "0603_SHORT_Y")
      (libsource (lib "YaoZhenSch") (part "SHORT"))
    )
    (comp (ref "T1") (value "SVS0") (footprint "TEST_PT") (libsource (lib "FM301_TEST") (part "TEST_POINT2")))
    (comp (ref "T2") (value "SVS1") (footprint "TEST_PT") (libsource (lib "FM301_TEST") (part "TEST_POINT2")))
    (comp (ref "T3")
      (value "318_RXD0")
      (footprint "TEST_PT")
      (libsource (lib "FM301_Verification") (part "TEST_POINT"))
    )
    (comp (ref "T4")
      (value "318_TXD0")
      (footprint "TEST_PT")
      (libsource (lib "FM301_Verification") (part "TEST_POINT"))
    )
    (comp (ref "T5")
      (value "BUF4TST")
      (footprint "TEST_PT")
      (libsource (lib "FM301_TEST") (part "TEST_POINT2"))
    )
    (comp (ref "T6")
      (value "VIN5V")
      (footprint "TEST_PT")
      (libsource (lib "FM301_Verification") (part "TEST_POINT"))
    )
    (comp (ref "T7")
      (value "+5V")
      (footprint "TEST_PT")
      (libsource (lib "FM301_Verification") (part "TEST_POINT"))
    )
    (comp (ref "T8")
      (value "318_TXD1")
      (footprint "TEST_PT")
      (libsource (lib "FM301_Verification") (part "TEST_POINT"))
    )
    (comp (ref "T9")
      (value "318_RXD1")
      (footprint "TEST_PT")
      (libsource (lib "FM301_Verification") (part "TEST_POINT"))
    )
    (comp (ref "T10")
      (value "ADCIN2")
      (footprint "TEST_PT")
      (libsource (lib "FM301_TEST") (part "TEST_POINT2"))
    )
    (comp (ref "T11")
      (value "ADCIN0")
      (footprint "TEST_PT")
      (libsource (lib "FM301_TEST") (part "TEST_POINT2"))
    )
    (comp (ref "T12")
      (value "ADCIN1")
      (footprint "TEST_PT")
      (libsource (lib "FM301_TEST") (part "TEST_POINT2"))
    )
    (comp (ref "T15")
      (value "FOUT1")
      (footprint "TEST_PT")
      (libsource (lib "FM301_TEST") (part "TEST_POINT2"))
    )
    (comp (ref "T16")
      (value "FOUT0")
      (footprint "TEST_PT")
      (libsource (lib "FM301_TEST") (part "TEST_POINT2"))
    )
    (comp (ref "T17")
      (value "IT2CKOUT")
      (footprint "TEST_PT")
      (libsource (lib "FM301_TEST") (part "TEST_POINT2"))
    )
    (comp (ref "T18")
      (value "FOUT0")
      (footprint "TEST_PT")
      (libsource (lib "FM301_TEST") (part "TEST_POINT2"))
    )
    (comp (ref "T20")
      (value "IN+")
      (footprint "TEST_PT")
      (libsource (lib "FM301_Verification") (part "TEST_POINT"))
    )
    (comp (ref "U1")
      (value "FM375_SOCKET108")
      (footprint "SOCKET108_LARGE")
      (libsource (lib "FM375_SOCKET") (part "FM375_SOCKET108"))
    )
    (comp (ref "U2") (value "24C32") (footprint "SOIC8_SOP8") (libsource (lib "*") (part "24CXX")))
    (comp (ref "U3")
      (value "MAX232CSE")
      (footprint "NSO16_M")
      (description "CI-MAX232CPE")
      (libsource (lib "集成电路") (part "MAX232CPE"))
    )
    (comp (ref "U4")
      (value "MAX232CSE")
      (footprint "NSO16_M")
      (description "CI-MAX232CPE")
      (libsource (lib "集成电路") (part "MAX232CPE"))
    )
    (comp (ref "U5")
      (value "MAX232CSE")
      (footprint "NSO16_M")
      (description "CI-MAX232CPE")
      (libsource (lib "集成电路") (part "MAX232CPE"))
    )
    (comp (ref "U6") (value "25D40VS") (footprint "SOP8-1.27") (libsource (lib "Z8D64U") (part "25D40VS")))
    (comp (ref "U7")
      (value "FM318_LQFP80")
      (footprint "LQFP80_12x12")
      (libsource (lib "FM318_SOCKET") (part "FM318_LQFP80"))
    )
    (comp (ref "U8")
      (value "OPA237")
      (footprint "OPA237_SO8")
      (libsource (lib "FM340_TEST") (part "OPA2237"))
    )
    (comp (ref "U17") (value "MAX312L") (footprint "TSSOP16") (libsource (lib "zgq") (part "MAX312L")))
    (comp (ref "V1") (value "LED") (footprint "LED-DIODE0.1-BIGHOLE") (libsource (lib "*") (part "LED")))
    (comp (ref "V2") (value "LED") (footprint "LED-DIODE0.1-BIGHOLE") (libsource (lib "*") (part "LED")))
    (comp (ref "V3") (value "LED") (footprint "LED-DIODE0.1-BIGHOLE") (libsource (lib "*") (part "LED")))
    (comp (ref "V4") (value "LED") (footprint "LED-DIODE0.1-BIGHOLE") (libsource (lib "*") (part "LED")))
    (comp (ref "XTAL1")
      (value "32K")
      (footprint "XTAL-RB32K_2")
      (description "Crystal")
      (libsource (lib "FM301_TEST") (part "CRYSTAL"))
    )
    (comp (ref "XTAL2")
      (value "8M")
      (footprint "XTAL-RAD0.2")
      (description "Crystal")
      (libsource (lib "FM301_TEST") (part "CRYSTAL"))
    )
    (comp (ref "Z1") (value "MBs") (footprint "0603") (libsource (lib "YaoZhenSch") (part "MBs")))
    (comp (ref "Z2") (value "MBs") (footprint "0603") (libsource (lib "YaoZhenSch") (part "MBs")))
    (comp (ref "Z3") (value "MBs") (footprint "0603") (libsource (lib "YaoZhenSch") (part "MBs")))
  )
  (nets
    (net (code "1") (name "-5V") (class "Default")
      (node (ref "C26") (pin "2") (pinfunction "2_2") (pintype "passive"))
      (node (ref "C41") (pin "1") (pinfunction "1_1") (pintype "passive"))
      (node (ref "P26") (pin "2") (pinfunction "2_2") (pintype "passive"))
      (node (ref "R19") (pin "2") (pinfunction "2_2") (pintype "passive"))
      (node (ref "U17") (pin "4") (pinfunction "V-_4") (pintype "passive"))
      (node (ref "U8") (pin "4") (pinfunction "V-_4") (pintype "passive"))
    )
    (net (code "2") (name "-VCC5V") (class "Default")
      (node (ref "-5V") (pin "1") (pinfunction "1_1") (pintype "passive"))
      (node (ref "C39") (pin "1") (pinfunction "1_1") (pintype "passive"))
      (node (ref "C40") (pin "2") (pinfunction "2_2") (pintype "passive"))
      (node (ref "D10") (pin "K") (pinfunction "2_K") (pintype "passive"))
      (node (ref "J11") (pin "1") (pinfunction "1_1") (pintype "passive"))
      (node (ref "J11") (pin "2") (pinfunction "2_2") (pintype "passive"))
      (node (ref "P26") (pin "1") (pinfunction "1_1") (pintype "passive"))
      (node (ref "S7") (pin "1") (pinfunction "1_1") (pintype "passive"))
    )
    (net (code "3") (name "/7816CLK") (class "Default")
      (node (ref "P3") (pin "17") (pinfunction "17_17") (pintype "passive"))
      (node (ref "P30") (pin "8") (pinfunction "8_8") (pintype "passive"))
      (node (ref "U1") (pin "59") (pinfunction "PE0/7816CLK/P2.0_59") (pintype "passive"))
    )
    (net (code "4") (name "/7816IO0") (class "Default")
      (node (ref "P3") (pin "16") (pinfunction "16_16") (pintype "passive"))
      (node (ref "P30") (pin "12") (pinfunction "12_12") (pintype "passive"))
      (node (ref "U1") (pin "60") (pinfunction "PE1/7816IO0/P2.1_60") (pintype "passive"))
    )
    (net (code "5") (name "/7816IO1") (class "Default")
      (node (ref "P3") (pin "15") (pinfunction "15_15") (pintype "passive"))
      (node (ref "P30") (pin "6") (pinfunction "6_6") (pintype "passive"))
      (node (ref "U1") (pin "61") (pinfunction "PE2/7816IO1/P2.2_61") (pintype "passive"))
    )
    (net (code "6") (name "/7816RST") (class "Default")
      (node (ref "P17") (pin "22") (pinfunction "SEG18_22") (pintype "passive"))
      (node (ref "P3") (pin "14") (pinfunction "14_14") (pintype "passive"))
      (node (ref "P30") (pin "10") (pinfunction "10_10") (pintype "passive"))
      (node (ref "U1") (pin "62") (pinfunction "PE3/T12IN2/SEG18/P2.3_62") (pintype "passive"))
    )
    (net (code "7") (name "/ADC0") (class "Default")
      (node (ref "P17") (pin "13") (pinfunction "SEG9_13") (pintype "passive"))
      (node (ref "P2") (pin "3") (pinfunction "3_3") (pintype "passive"))
      (node (ref "S3") (pin "1") (pinfunction "1_1") (pintype "passive"))
      (node (ref "T11") (pin "1") (pinfunction "1_1") (pintype "passive"))
      (node (ref "U1") (pin "32") (pinfunction "PC1/SEG9/AN0/P1.1_32") (pintype "passive"))
    )
    (net (code "8") (name "/ADC1") (class "Default")
      (node (ref "P31") (pin "2") (pinfunction "2_2") (pintype "passive"))
      (node (ref "P4") (pin "1") (pinfunction "1_1") (pintype "passive"))
      (node (ref "S4") (pin "1") (pinfunction "1_1") (pintype "passive"))
      (node (ref "T12") (pin "1") (pinfunction "1_1") (pintype "passive"))
      (node (ref "U1") (pin "103") (pinfunction "PCACOMP1/AN1/PF7(BOOT0)_103") (pintype "passive"))
    )
    (net (code "9") (name "/ADC2") (class "Default")
      (node (ref "C15") (pin "2") (pinfunction "2_2") (pintype "passive"))
      (node (ref "P10") (pin "1") (pinfunction "1_1") (pintype "passive"))
      (node (ref "P3") (pin "4") (pinfunction "4_4") (pintype "passive"))
      (node (ref "S2") (pin "1") (pinfunction "1_1") (pintype "passive"))
      (node (ref "T10") (pin "1") (pinfunction "1_1") (pintype "passive"))
      (node (ref "T16") (pin "1") (pinfunction "1_1") (pintype "passive"))
      (node (ref "U1") (pin "72") (pinfunction "PF5/PCAECI/AN2(VCIN2)/FOUT0_72") (pintype "passive"))
    )
    (net (code "10") (name "/BD_TCK") (class "Default")
      (node (ref "J1") (pin "11") (pinfunction "11_11") (pintype "passive"))
      (node (ref "P4") (pin "7") (pinfunction "7_7") (pintype "passive"))
      (node (ref "U1") (pin "97") (pinfunction "TCK(TCLK)/RXD3/PG2_97") (pintype "passive"))
    )
    (net (code "11") (name "/BD_TDI") (class "Default")
      (node (ref "J1") (pin "5") (pinfunction "5_5") (pintype "passive"))
      (node (ref "P4") (pin "9") (pinfunction "9_9") (pintype "passive"))
      (node (ref "U1") (pin "95") (pinfunction "TDI(STROBE)/RXD2/PG0_95") (pintype "passive"))
    )
    (net (code "12") (name "/BD_TDO") (class "Default")
      (node (ref "J1") (pin "13") (pinfunction "13_13") (pintype "passive"))
      (node (ref "JP1") (pin "1") (pinfunction "1_1") (pintype "passive"))
      (node (ref "P4") (pin "6") (pinfunction "6_6") (pintype "passive"))
      (node (ref "U1") (pin "98") (pinfunction "TDO(TDIO)/TXD3/PG3_98") (pintype "passive"))
    )
    (net (code "13") (name "/BD_TMS") (class "Default")
      (node (ref "J1") (pin "9") (pinfunction "9_9") (pintype "passive"))
      (node (ref "P4") (pin "8") (pinfunction "8_8") (pintype "passive"))
      (node (ref "U1") (pin "96") (pinfunction "TMS/TXD2/PG1_96") (pintype "passive"))
    )
    (net (code "14") (name "/COM0") (class "Default")
      (node (ref "P1") (pin "1") (pinfunction "1_1") (pintype "passive"))
      (node (ref "P15") (pin "1") (pinfunction "1_1") (pintype "passive"))
      (node (ref "P17") (pin "1") (pinfunction "COM0_1") (pintype "passive"))
      (node (ref "P20") (pin "5") (pinfunction "5_5") (pintype "passive"))
      (node (ref "U1") (pin "3") (pinfunction "RXD1/MOSI/COM0/PA0_3") (pintype "passive"))
    )
    (net (code "15") (name "/COM1") (class "Default")
      (node (ref "P1") (pin "2") (pinfunction "2_2") (pintype "passive"))
      (node (ref "P15") (pin "3") (pinfunction "3_3") (pintype "passive"))
      (node (ref "P17") (pin "2") (pinfunction "COM1_2") (pintype "passive"))
      (node (ref "P20") (pin "3") (pinfunction "3_3") (pintype "passive"))
      (node (ref "U1") (pin "4") (pinfunction "TXD1/MISO/COM1/PA1_4") (pintype "passive"))
    )
    (net (code "16") (name "/COM2") (class "Default")
      (node (ref "P1") (pin "3") (pinfunction "3_3") (pintype "passive"))
      (node (ref "P17") (pin "3") (pinfunction "COM2_3") (pintype "passive"))
      (node (ref "P20") (pin "7") (pinfunction "7_7") (pintype "passive"))
      (node (ref "U1") (pin "5") (pinfunction "PCACOMP0/SCK/COM2/PA2_5") (pintype "passive"))
    )
    (net (code "17") (name "/COM3") (class "Default")
      (node (ref "P1") (pin "4") (pinfunction "4_4") (pintype "passive"))
      (node (ref "P17") (pin "4") (pinfunction "COM3_4") (pintype "passive"))
      (node (ref "P5") (pin "2") (pinfunction "2_2") (pintype "passive"))
      (node (ref "U1") (pin "6") (pinfunction "PCACOMP1/SSN/COM3/PA3_6") (pintype "passive"))
    )
    (net (code "18") (name "/CPLL") (class "Default")
      (node (ref "P4") (pin "12") (pinfunction "12_12") (pintype "passive"))
      (node (ref "U1") (pin "92") (pinfunction "CPLL_92") (pintype "passive"))
    )
    (net (code "19") (name "/C_Chanel") (class "Default")
      (node (ref "R10") (pin "2") (pinfunction "2_2") (pintype "passive"))
      (node (ref "U17") (pin "2") (pinfunction "COM1_2") (pintype "passive"))
    )
    (net (code "20") (name "/D_Chanel") (class "Default")
      (node (ref "R15") (pin "1") (pinfunction "1_1") (pintype "passive"))
      (node (ref "U17") (pin "14") (pinfunction "NO2_14") (pintype "passive"))
    )
    (net (code "21") (name "/FM318_RXD0") (class "Default")
      (node (ref "T3") (pin "1") (pinfunction "1_1") (pintype "passive"))
      (node (ref "U5") (pin "9") (pinfunction "R2OUT_9") (pintype "passive"))
      (node (ref "U7") (pin "17") (pinfunction "GPIO14/RXD0/P04_17") (pintype "bidirectional"))
    )
    (net (code "22") (name "/FM318_RXD1") (class "Default")
      (node (ref "T9") (pin "1") (pinfunction "1_1") (pintype "passive"))
      (node (ref "U5") (pin "12") (pinfunction "R1OUT_12") (pintype "passive"))
      (node (ref "U7") (pin "9") (pinfunction "GPIO06/RXD1/SEG0_9") (pintype "bidirectional"))
    )
    (net (code "23") (name "/FM318_RXD2") (class "Default")
      (node (ref "P28") (pin "3") (pinfunction "3_3") (pintype "passive"))
      (node (ref "U7") (pin "39") (pinfunction "GPIO36/RXD2/P36_39") (pintype "bidirectional"))
    )
    (net (code "24") (name "/FM318_TXD0") (class "Default")
      (node (ref "T4") (pin "1") (pinfunction "1_1") (pintype "passive"))
      (node (ref "U5") (pin "10") (pinfunction "T2IN_10") (pintype "passive"))
      (node (ref "U7") (pin "18") (pinfunction "GPIO15/TXD0/P05_18") (pintype "bidirectional"))
    )
    (net (code "25") (name "/FM318_TXD1") (class "Default")
      (node (ref "T8") (pin "1") (pinfunction "1_1") (pintype "passive"))
      (node (ref "U5") (pin "11") (pinfunction "T1IN_11") (pintype "passive"))
      (node (ref "U7") (pin "10") (pinfunction "GPIO07/TXD1/SEG1_10") (pintype "bidirectional"))
    )
    (net (code "26") (name "/FM318_TXD2") (class "Default")
      (node (ref "P28") (pin "1") (pinfunction "1_1") (pintype "passive"))
      (node (ref "U7") (pin "40") (pinfunction "GPIO37/TXD2/P37_40") (pintype "bidirectional"))
    )
    (net (code "27") (name "/FM375_RXD0") (class "Default")
      (node (ref "P12") (pin "2") (pinfunction "2_2") (pintype "passive"))
      (node (ref "U4") (pin "9") (pinfunction "R2OUT_9") (pintype "passive"))
    )
    (net (code "28") (name "/FM375_RXD1") (class "Default")
      (node (ref "P15") (pin "2") (pinfunction "2_2") (pintype "passive"))
      (node (ref "U3") (pin "9") (pinfunction "R2OUT_9") (pintype "passive"))
    )
    (net (code "29") (name "/FM375_RXD2") (class "Default")
      (node (ref "P12") (pin "6") (pinfunction "6_6") (pintype "passive"))
      (node (ref "U4") (pin "12") (pinfunction "R1OUT_12") (pintype "passive"))
    )
    (net (code "30") (name "/FM375_RXD3") (class "Default")
      (node (ref "P15") (pin "6") (pinfunction "6_6") (pintype "passive"))
      (node (ref "U3") (pin "12") (pinfunction "R1OUT_12") (pintype "passive"))
    )
    (net (code "31") (name "/FM375_TXD0") (class "Default")
      (node (ref "P12") (pin "4") (pinfunction "4_4") (pintype "passive"))
      (node (ref "U4") (pin "10") (pinfunction "T2IN_10") (pintype "passive"))
    )
    (net (code "32") (name "/FM375_TXD1") (class "Default")
      (node (ref "P15") (pin "4") (pinfunction "4_4") (pintype "passive"))
      (node (ref "U3") (pin "10") (pinfunction "T2IN_10") (pintype "passive"))
    )
    (net (code "33") (name "/FM375_TXD2") (class "Default")
      (node (ref "P12") (pin "8") (pinfunction "8_8") (pintype "passive"))
      (node (ref "U4") (pin "11") (pinfunction "T1IN_11") (pintype "passive"))
    )
    (net (code "34") (name "/FM375_TXD3") (class "Default")
      (node (ref "P15") (pin "8") (pinfunction "8_8") (pintype "passive"))
      (node (ref "U3") (pin "11") (pinfunction "T1IN_11") (pintype "passive"))
    )
    (net (code "35") (name "/FOUT") (class "Default")
      (node (ref "P16") (pin "1") (pinfunction "1_1") (pintype "passive"))
      (node (ref "U7") (pin "2") (pinfunction "GPIO71/SEG37/FOUT_2") (pintype "bidirectional"))
    )
    (net (code "36") (name "/GPIO20") (class "Default")
      (node (ref "P13") (pin "1") (pinfunction "1_1") (pintype "passive"))
      (node (ref "U7") (pin "21") (pinfunction "GPIO20/ECI/SEG8/TESTCLK/P10_21") (pintype "bidirectional"))
    )
    (net (code "37") (name "/GPIO21") (class "Default")
      (node (ref "P13") (pin "2") (pinfunction "2_2") (pintype "passive"))
      (node (ref "U7") (pin "22") (pinfunction "GPIO21/SEG9/EXOUT1/P11_22") (pintype "bidirectional"))
    )
    (net (code "38") (name "/GPIO22") (class "Default")
      (node (ref "P13") (pin "3") (pinfunction "3_3") (pintype "passive"))
      (node (ref "U7") (pin "23") (pinfunction "GPIO22/SEG10/PCACOMP0/P12_23") (pintype "bidirectional"))
    )
    (net (code "39") (name "/GPIO23") (class "Default")
      (node (ref "P13") (pin "4") (pinfunction "4_4") (pintype "passive"))
      (node (ref "U7") (pin "24") (pinfunction "GPIO23/SEG11/PCACOMP1/SCANIN[1]/P13_24") (pintype "bidirectional"))
    )
    (net (code "40") (name "/GPIO24") (class "Default")
      (node (ref "P13") (pin "5") (pinfunction "5_5") (pintype "passive"))
      (node (ref "U7") (pin "25") (pinfunction "GPIO24/SEG12/EXIN4/P14_25") (pintype "bidirectional"))
    )
    (net (code "41") (name "/GPIO25") (class "Default")
      (node (ref "P13") (pin "6") (pinfunction "6_6") (pintype "passive"))
      (node (ref "U7") (pin "26") (pinfunction "GPIO25/SEG13/EXIN3/SCANIN[0]/P15_26") (pintype "bidirectional"))
    )
    (net (code "42") (name "/GPIO26") (class "Default")
      (node (ref "P13") (pin "7") (pinfunction "7_7") (pintype "passive"))
      (node (ref "U7") (pin "27") (pinfunction "GPIO26/SEG14/EXIN2/P16_27") (pintype "bidirectional"))
    )
    (net (code "43") (name "/GPIO27") (class "Default")
      (node (ref "P13") (pin "8") (pinfunction "8_8") (pintype "passive"))
      (node (ref "U7") (pin "28") (pinfunction "GPIO27/SEG15/EXIN1/SCANOUT[1]/P17_28") (pintype "bidirectional"))
    )
    (net (code "44") (name "/GPIO31") (class "Default")
      (node (ref "P14") (pin "5") (pinfunction "5_5") (pintype "passive"))
      (node (ref "U7") (pin "34") (pinfunction "GPIO31/REMAP1/SEG17/P31_34") (pintype "bidirectional"))
    )
    (net (code "45") (name "/GPIO32") (class "Default")
      (node (ref "P14") (pin "6") (pinfunction "6_6") (pintype "passive"))
      (node (ref "U7") (pin "35") (pinfunction "GPIO32/TM1/SEG18/P32_35") (pintype "bidirectional"))
    )
    (net (code "46") (name "/GPIO40") (class "Default")
      (node (ref "P27") (pin "1") (pinfunction "1_1") (pintype "passive"))
      (node (ref "U7") (pin "41") (pinfunction "GPIO40/7816_CLK_41") (pintype "bidirectional"))
    )
    (net (code "47") (name "/GPIO41") (class "Default")
      (node (ref "P27") (pin "2") (pinfunction "2_2") (pintype "passive"))
      (node (ref "U7") (pin "42") (pinfunction "GPIO41/7816_IO0/POR_42") (pintype "bidirectional"))
    )
    (net (code "48") (name "/GPIO42") (class "Default")
      (node (ref "P27") (pin "3") (pinfunction "3_3") (pintype "passive"))
      (node (ref "U7") (pin "43") (pinfunction "GPIO42/7816_IO1/PDR_43") (pintype "bidirectional"))
    )
    (net (code "49") (name "/GPIO43") (class "Default")
      (node (ref "P27") (pin "4") (pinfunction "4_4") (pintype "passive"))
      (node (ref "U7") (pin "48") (pinfunction "GPIO43/SEG22/timer0_48") (pintype "bidirectional"))
    )
    (net (code "50") (name "/GPIO50") (class "Default")
      (node (ref "D1") (pin "K") (pinfunction "2_K") (pintype "passive"))
      (node (ref "U7") (pin "53") (pinfunction "GPIO50/SEG26/timer1gate/PF_n/AN3_53") (pintype "bidirectional"))
    )
    (net (code "51") (name "/GPIO51") (class "Default")
      (node (ref "D2") (pin "K") (pinfunction "2_K") (pintype "passive"))
      (node (ref "U7") (pin "54") (pinfunction "GPIO51/SEG27/AN4/SVS0_54") (pintype "bidirectional"))
    )
    (net (code "52") (name "/GPIO52") (class "Default")
      (node (ref "D3") (pin "K") (pinfunction "2_K") (pintype "passive"))
      (node (ref "U7") (pin "55") (pinfunction "GPIO52/SEG28/AN5/SVS1_55") (pintype "bidirectional"))
    )
    (net (code "53") (name "/GPIO53") (class "Default")
      (node (ref "D4") (pin "K") (pinfunction "2_K") (pintype "passive"))
      (node (ref "U7") (pin "56") (pinfunction "GPIO53/SEG29/AN6_56") (pintype "bidirectional"))
    )
    (net (code "54") (name "/GPIO74") (class "Default")
      (node (ref "P14") (pin "1") (pinfunction "1_1") (pintype "passive"))
      (node (ref "U7") (pin "29") (pinfunction "GPIO74/MOSI/P00_29") (pintype "bidirectional"))
    )
    (net (code "55") (name "/GPIO75") (class "Default")
      (node (ref "P14") (pin "2") (pinfunction "2_2") (pintype "passive"))
      (node (ref "U7") (pin "30") (pinfunction "GPIO75/MISO/SCANOUT[0]/P01_30") (pintype "bidirectional"))
    )
    (net (code "56") (name "/GPIO76") (class "Default")
      (node (ref "P14") (pin "3") (pinfunction "3_3") (pintype "passive"))
      (node (ref "U7") (pin "31") (pinfunction "GPIO76/SCK/P02_31") (pintype "bidirectional"))
    )
    (net (code "57") (name "/GPIO77") (class "Default")
      (node (ref "P14") (pin "4") (pinfunction "4_4") (pintype "passive"))
      (node (ref "U7") (pin "32") (pinfunction "GPIO77/SSN/P03_32") (pintype "bidirectional"))
    )
    (net (code "58") (name "/I2C_SCL") (class "Default")
      (node (ref "P11") (pin "4") (pinfunction "4_4") (pintype "passive"))
      (node (ref "R29") (pin "2") (pinfunction "2_2") (pintype "passive"))
    )
    (net (code "59") (name "/I2C_SDA") (class "Default")
      (node (ref "P11") (pin "2") (pinfunction "2_2") (pintype "passive"))
      (node (ref "R30") (pin "1") (pinfunction "1_1") (pintype "passive"))
    )
    (net (code "60") (name "/IN+") (class "Default")
      (node (ref "R32") (pin "2") (pinfunction "2_2") (pintype "passive"))
      (node (ref "T20") (pin "1") (pinfunction "1_1") (pintype "passive"))
      (node (ref "U17") (pin "15") (pinfunction "COM2_15") (pintype "passive"))
      (node (ref "U17") (pin "3") (pinfunction "NO1_3") (pintype "passive"))
    )
    (net (code "61") (name "/KEY1") (class "Default")
      (node (ref "C50") (pin "1") (pinfunction "1_1") (pintype "passive"))
      (node (ref "K1") (pin "1") (pinfunction "1_1") (pintype "passive"))
      (node (ref "P19") (pin "1") (pinfunction "1_1") (pintype "passive"))
      (node (ref "R40") (pin "1") (pinfunction "1_1") (pintype "passive"))
    )
    (net (code "62") (name "/KEY2") (class "Default")
      (node (ref "C51") (pin "1") (pinfunction "1_1") (pintype "passive"))
      (node (ref "K2") (pin "1") (pinfunction "1_1") (pintype "passive"))
      (node (ref "P19") (pin "3") (pinfunction "3_3") (pintype "passive"))
      (node (ref "R41") (pin "1") (pinfunction "1_1") (pintype "passive"))
    )
    (net (code "63") (name "/KEY3") (class "Default")
      (node (ref "C52") (pin "1") (pinfunction "1_1") (pintype "passive"))
      (node (ref "K3") (pin "1") (pinfunction "1_1") (pintype "passive"))
      (node (ref "P19") (pin "5") (pinfunction "5_5") (pintype "passive"))
      (node (ref "R42") (pin "1") (pinfunction "1_1") (pintype "passive"))
    )
    (net (code "64") (name "/KEY4") (class "Default")
      (node (ref "C53") (pin "1") (pinfunction "1_1") (pintype "passive"))
      (node (ref "K4") (pin "1") (pinfunction "1_1") (pintype "passive"))
      (node (ref "P19") (pin "7") (pinfunction "7_7") (pintype "passive"))
      (node (ref "R43") (pin "1") (pinfunction "1_1") (pintype "passive"))
    )
    (net (code "65") (name "/KEY5") (class "Default")
      (node (ref "C54") (pin "2") (pinfunction "2_2") (pintype "passive"))
      (node (ref "K5") (pin "2") (pinfunction "2_2") (pintype "passive"))
      (node (ref "P19") (pin "9") (pinfunction "9_9") (pintype "passive"))
      (node (ref "R44") (pin "2") (pinfunction "2_2") (pintype "passive"))
    )
    (net (code "66") (name "/KEY6") (class "Default")
      (node (ref "C55") (pin "2") (pinfunction "2_2") (pintype "passive"))
      (node (ref "K6") (pin "2") (pinfunction "2_2") (pintype "passive"))
      (node (ref "P19") (pin "11") (pinfunction "11_11") (pintype "passive"))
      (node (ref "R45") (pin "2") (pinfunction "2_2") (pintype "passive"))
    )
    (net (code "67") (name "/KEY7") (class "Default")
      (node (ref "C56") (pin "2") (pinfunction "2_2") (pintype "passive"))
      (node (ref "K7") (pin "2") (pinfunction "2_2") (pintype "passive"))
      (node (ref "P19") (pin "13") (pinfunction "13_13") (pintype "passive"))
      (node (ref "R46") (pin "2") (pinfunction "2_2") (pintype "passive"))
    )
    (net (code "68") (name "/KEY8") (class "Default")
      (node (ref "C57") (pin "2") (pinfunction "2_2") (pintype "passive"))
      (node (ref "K8") (pin "2") (pinfunction "2_2") (pintype "passive"))
      (node (ref "P19") (pin "15") (pinfunction "15_15") (pintype "passive"))
      (node (ref "R47") (pin "2") (pinfunction "2_2") (pintype "passive"))
    )
    (net (code "69") (name "/LED1") (class "Default")
      (node (ref "P9") (pin "8") (pinfunction "8_8") (pintype "passive"))
      (node (ref "V1") (pin "K") (pinfunction "2_K") (pintype "passive"))
    )
    (net (code "70") (name "/LED2") (class "Default")
      (node (ref "P9") (pin "6") (pinfunction "6_6") (pintype "passive"))
      (node (ref "V2") (pin "K") (pinfunction "2_K") (pintype "passive"))
    )
    (net (code "71") (name "/LED3") (class "Default")
      (node (ref "P9") (pin "4") (pinfunction "4_4") (pintype "passive"))
      (node (ref "V3") (pin "K") (pinfunction "2_K") (pintype "passive"))
    )
    (net (code "72") (name "/LED4") (class "Default")
      (node (ref "P9") (pin "2") (pinfunction "2_2") (pintype "passive"))
      (node (ref "V4") (pin "K") (pinfunction "2_K") (pintype "passive"))
    )
    (net (code "73") (name "/MISO_flash") (class "Default")
      (node (ref "P20") (pin "4") (pinfunction "4_4") (pintype "passive"))
      (node (ref "U6") (pin "2") (pinfunction "DO_IO1_2") (pintype "output"))
    )
    (net (code "74") (name "/MOSI_flash") (class "Default")
      (node (ref "P20") (pin "6") (pinfunction "6_6") (pintype "passive"))
      (node (ref "U6") (pin "5") (pinfunction "DIO_IO0_5") (pintype "bidirectional"))
    )
    (net (code "75") (name "/NEG") (class "Default")
      (node (ref "C16") (pin "1") (pinfunction "1_1") (pintype "passive"))
      (node (ref "NEG") (pin "2") (pinfunction "2_2") (pintype "passive"))
      (node (ref "R31") (pin "1") (pinfunction "1_1") (pintype "passive"))
      (node (ref "U7") (pin "38") (pinfunction "GPIO35/SEG21/PCACOMP4/P35_38") (pintype "bidirectional"))
    )
    (net (code "76") (name "/OSCIN") (class "Default")
      (node (ref "C22") (pin "1") (pinfunction "1_1") (pintype "passive"))
      (node (ref "R20") (pin "2") (pinfunction "2_2") (pintype "passive"))
      (node (ref "U7") (pin "73") (pinfunction "GPIO60/OSCIN_73") (pintype "bidirectional"))
      (node (ref "XTAL2") (pin "2") (pinfunction "2_2") (pintype "passive"))
    )
    (net (code "77") (name "/OSCOUT") (class "Default")
      (node (ref "C23") (pin "1") (pinfunction "1_1") (pintype "passive"))
      (node (ref "R20") (pin "1") (pinfunction "1_1") (pintype "passive"))
      (node (ref "U7") (pin "74") (pinfunction "GPIO61/OSCOUT_74") (pintype "bidirectional"))
      (node (ref "XTAL2") (pin "1") (pinfunction "1_1") (pintype "passive"))
    )
    (net (code "78") (name "/PA4") (class "Default")
      (node (ref "P1") (pin "5") (pinfunction "5_5") (pintype "passive"))
      (node (ref "P17") (pin "28") (pinfunction "SEG24_28") (pintype "passive"))
      (node (ref "P20") (pin "1") (pinfunction "1_1") (pintype "passive"))
      (node (ref "P9") (pin "7") (pinfunction "7_7") (pintype "passive"))
      (node (ref "U1") (pin "7") (pinfunction "PCACOMP2/COM4/SEG24/PA4_7") (pintype "passive"))
    )
    (net (code "79") (name "/PA5") (class "Default")
      (node (ref "P1") (pin "6") (pinfunction "6_6") (pintype "passive"))
      (node (ref "P17") (pin "29") (pinfunction "SEG25_29") (pintype "passive"))
      (node (ref "P9") (pin "5") (pinfunction "5_5") (pintype "passive"))
      (node (ref "U1") (pin "8") (pinfunction "PCACAPT4/COM5/SEG25/PA5_8") (pintype "passive"))
    )
    (net (code "80") (name "/PA6") (class "Default")
      (node (ref "P1") (pin "7") (pinfunction "7_7") (pintype "passive"))
      (node (ref "P9") (pin "3") (pinfunction "3_3") (pintype "passive"))
      (node (ref "U1") (pin "9") (pinfunction "PCACAPT0/SEG0/P0.6/PA6_9") (pintype "passive"))
    )
    (net (code "81") (name "/PA7") (class "Default")
      (node (ref "P1") (pin "8") (pinfunction "8_8") (pintype "passive"))
      (node (ref "P17") (pin "5") (pinfunction "SEG1_5") (pintype "passive"))
      (node (ref "P9") (pin "1") (pinfunction "1_1") (pintype "passive"))
      (node (ref "U1") (pin "10") (pinfunction "T12IN0/SEG1/P0.7/PA7_10") (pintype "passive"))
    )
    (net (code "82") (name "/PB0") (class "Default")
      (node (ref "P1") (pin "9") (pinfunction "9_9") (pintype "passive"))
      (node (ref "P17") (pin "6") (pinfunction "SEG2_6") (pintype "passive"))
      (node (ref "P19") (pin "2") (pinfunction "2_2") (pintype "passive"))
      (node (ref "U1") (pin "11") (pinfunction "RXD0/SEG2/P0.0/PB0_11") (pintype "passive"))
    )
    (net (code "83") (name "/PB1") (class "Default")
      (node (ref "P1") (pin "10") (pinfunction "10_10") (pintype "passive"))
      (node (ref "P17") (pin "7") (pinfunction "SEG3_7") (pintype "passive"))
      (node (ref "P19") (pin "4") (pinfunction "4_4") (pintype "passive"))
      (node (ref "U1") (pin "12") (pinfunction "TXD0/SEG3/P0.1/PB1_12") (pintype "passive"))
    )
    (net (code "84") (name "/PB2") (class "Default")
      (node (ref "P1") (pin "11") (pinfunction "11_11") (pintype "passive"))
      (node (ref "P17") (pin "8") (pinfunction "SEG4_8") (pintype "passive"))
      (node (ref "P19") (pin "6") (pinfunction "6_6") (pintype "passive"))
      (node (ref "U1") (pin "13") (pinfunction "7816CLK/SEG4/P0.2/PB2_13") (pintype "passive"))
    )
    (net (code "85") (name "/PB3") (class "Default")
      (node (ref "P1") (pin "12") (pinfunction "12_12") (pintype "passive"))
      (node (ref "P17") (pin "9") (pinfunction "SEG5_9") (pintype "passive"))
      (node (ref "P19") (pin "8") (pinfunction "8_8") (pintype "passive"))
      (node (ref "U1") (pin "14") (pinfunction "7816IO0/SEG5/P0.3/PB3_14") (pintype "passive"))
    )
    (net (code "86") (name "/PB4") (class "Default")
      (node (ref "P1") (pin "13") (pinfunction "13_13") (pintype "passive"))
      (node (ref "P17") (pin "10") (pinfunction "SEG6_10") (pintype "passive"))
      (node (ref "P19") (pin "10") (pinfunction "10_10") (pintype "passive"))
      (node (ref "U1") (pin "15") (pinfunction "LPTI/SEG6/P0.4/PB4_15") (pintype "passive"))
    )
    (net (code "87") (name "/PB5") (class "Default")
      (node (ref "P1") (pin "14") (pinfunction "14_14") (pintype "passive"))
      (node (ref "P17") (pin "11") (pinfunction "SEG7_11") (pintype "passive"))
      (node (ref "P19") (pin "12") (pinfunction "12_12") (pintype "passive"))
      (node (ref "U1") (pin "16") (pinfunction "LPTOUT/SEG7/P0.5/PB5_16") (pintype "passive"))
    )
    (net (code "88") (name "/PB6") (class "Default")
      (node (ref "P1") (pin "15") (pinfunction "15_15") (pintype "passive"))
      (node (ref "P19") (pin "14") (pinfunction "14_14") (pintype "passive"))
      (node (ref "U1") (pin "17") (pinfunction "LPTRG/SCL/PB6_17") (pintype "passive"))
    )
    (net (code "89") (name "/PB7") (class "Default")
      (node (ref "P1") (pin "16") (pinfunction "16_16") (pintype "passive"))
      (node (ref "P19") (pin "16") (pinfunction "16_16") (pintype "passive"))
      (node (ref "U1") (pin "18") (pinfunction "WKUP1/SDA/PB7_18") (pintype "passive"))
    )
    (net (code "90") (name "/PC0") (class "Default")
      (node (ref "P17") (pin "12") (pinfunction "SEG8_12") (pintype "passive"))
      (node (ref "P2") (pin "2") (pinfunction "2_2") (pintype "passive"))
      (node (ref "U1") (pin "31") (pinfunction "PC0/T12IN1/SEG8/P1.0_31") (pintype "passive"))
    )
    (net (code "91") (name "/PC2") (class "Default")
      (node (ref "P17") (pin "14") (pinfunction "SEG10_14") (pintype "passive"))
      (node (ref "P2") (pin "5") (pinfunction "5_5") (pintype "passive"))
      (node (ref "U1") (pin "35") (pinfunction "PC2/PCACOMP0/SEG10/P1.2_35") (pintype "passive"))
    )
    (net (code "92") (name "/PC3") (class "Default")
      (node (ref "P10") (pin "3") (pinfunction "3_3") (pintype "passive"))
      (node (ref "P17") (pin "15") (pinfunction "SEG11_15") (pintype "passive"))
      (node (ref "P2") (pin "6") (pinfunction "6_6") (pintype "passive"))
      (node (ref "T15") (pin "1") (pinfunction "1_1") (pintype "passive"))
      (node (ref "U1") (pin "36") (pinfunction "PC3/FOUT1/SEG11/P1.3_36") (pintype "passive"))
    )
    (net (code "93") (name "/PC4") (class "Default")
      (node (ref "P17") (pin "16") (pinfunction "SEG12_16") (pintype "passive"))
      (node (ref "P2") (pin "7") (pinfunction "7_7") (pintype "passive"))
      (node (ref "U1") (pin "37") (pinfunction "PC4/T4IN1/SEG12/P1.4_37") (pintype "passive"))
    )
    (net (code "94") (name "/PC5") (class "Default")
      (node (ref "P17") (pin "17") (pinfunction "SEG13_17") (pintype "passive"))
      (node (ref "P2") (pin "8") (pinfunction "8_8") (pintype "passive"))
      (node (ref "U1") (pin "38") (pinfunction "PC5/T4IN0/SEG13/P1.5_38") (pintype "passive"))
    )
    (net (code "95") (name "/PC6") (class "Default")
      (node (ref "P17") (pin "18") (pinfunction "SEG14_18") (pintype "passive"))
      (node (ref "P2") (pin "9") (pinfunction "9_9") (pintype "passive"))
      (node (ref "U1") (pin "39") (pinfunction "PC6/T3IN1/SEG14/P1.6_39") (pintype "passive"))
    )
    (net (code "96") (name "/PC7") (class "Default")
      (node (ref "P17") (pin "19") (pinfunction "SEG15_19") (pintype "passive"))
      (node (ref "P2") (pin "10") (pinfunction "10_10") (pintype "passive"))
      (node (ref "U1") (pin "40") (pinfunction "PC7/T3IN0/SEG15/P1.7_40") (pintype "passive"))
    )
    (net (code "97") (name "/PD0") (class "Default")
      (node (ref "P17") (pin "20") (pinfunction "SEG16_20") (pintype "passive"))
      (node (ref "P2") (pin "11") (pinfunction "11_11") (pintype "passive"))
      (node (ref "U1") (pin "41") (pinfunction "PD0/PCACAPT1/SEG16_41") (pintype "passive"))
    )
    (net (code "98") (name "/PD1") (class "Default")
      (node (ref "P17") (pin "21") (pinfunction "SEG17_21") (pintype "passive"))
      (node (ref "P2") (pin "12") (pinfunction "12_12") (pintype "passive"))
      (node (ref "U1") (pin "42") (pinfunction "PD1/SEG17/PCACAPT3/WKUP2_42") (pintype "passive"))
    )
    (net (code "99") (name "/PD2") (class "Default")
      (node (ref "P12") (pin "5") (pinfunction "5_5") (pintype "passive"))
      (node (ref "P2") (pin "13") (pinfunction "13_13") (pintype "passive"))
      (node (ref "U1") (pin "43") (pinfunction "PD2/RXD2/PCACOMP2_43") (pintype "passive"))
    )
    (net (code "100") (name "/PD3") (class "Default")
      (node (ref "P12") (pin "7") (pinfunction "7_7") (pintype "passive"))
      (node (ref "P2") (pin "14") (pinfunction "14_14") (pintype "passive"))
      (node (ref "P8") (pin "2") (pinfunction "2_2") (pintype "passive"))
      (node (ref "U1") (pin "44") (pinfunction "PD3/TXD2/PCACOMP3_44") (pintype "passive"))
    )
    (net (code "101") (name "/PD4") (class "Default")
      (node (ref "P2") (pin "15") (pinfunction "15_15") (pintype "passive"))
      (node (ref "P8") (pin "4") (pinfunction "4_4") (pintype "passive"))
      (node (ref "U1") (pin "45") (pinfunction "PD4/MOSI/T4IN1_45") (pintype "passive"))
    )
    (net (code "102") (name "/PD5") (class "Default")
      (node (ref "P2") (pin "16") (pinfunction "16_16") (pintype "passive"))
      (node (ref "P8") (pin "6") (pinfunction "6_6") (pintype "passive"))
      (node (ref "U1") (pin "46") (pinfunction "PD5/MISO/T4IN0_46") (pintype "passive"))
    )
    (net (code "103") (name "/PD6") (class "Default")
      (node (ref "P2") (pin "17") (pinfunction "17_17") (pintype "passive"))
      (node (ref "P8") (pin "8") (pinfunction "8_8") (pintype "passive"))
      (node (ref "U1") (pin "47") (pinfunction "PD6/SCK/T3IN1_47") (pintype "passive"))
    )
    (net (code "104") (name "/PD7") (class "Default")
      (node (ref "P2") (pin "18") (pinfunction "18_18") (pintype "passive"))
      (node (ref "P6") (pin "2") (pinfunction "2_2") (pintype "passive"))
      (node (ref "P8") (pin "10") (pinfunction "10_10") (pintype "passive"))
      (node (ref "U1") (pin "48") (pinfunction "PD7/SSN/T3IN0_48") (pintype "passive"))
    )
    (net (code "105") (name "/PE4") (class "Default")
      (node (ref "P17") (pin "23") (pinfunction "SEG19_23") (pintype "passive"))
      (node (ref "P3") (pin "13") (pinfunction "13_13") (pintype "passive"))
      (node (ref "U1") (pin "63") (pinfunction "PE4/T12IN3/SEG19/P2.4_63") (pintype "passive"))
    )
    (net (code "106") (name "/PE5") (class "Default")
      (node (ref "P11") (pin "3") (pinfunction "3_3") (pintype "passive"))
      (node (ref "P17") (pin "24") (pinfunction "SEG20_24") (pintype "passive"))
      (node (ref "P3") (pin "12") (pinfunction "12_12") (pintype "passive"))
      (node (ref "U1") (pin "64") (pinfunction "PE5/SEG20/P2.5/SCL_64") (pintype "passive"))
    )
    (net (code "107") (name "/PE6") (class "Default")
      (node (ref "P11") (pin "1") (pinfunction "1_1") (pintype "passive"))
      (node (ref "P17") (pin "25") (pinfunction "SEG21_25") (pintype "passive"))
      (node (ref "P3") (pin "11") (pinfunction "11_11") (pintype "passive"))
      (node (ref "U1") (pin "65") (pinfunction "PE6/SEG21/P2.6/SDA_65") (pintype "passive"))
    )
    (net (code "108") (name "/PE7") (class "Default")
      (node (ref "P17") (pin "26") (pinfunction "SEG22_26") (pintype "passive"))
      (node (ref "P3") (pin "10") (pinfunction "10_10") (pintype "passive"))
      (node (ref "U1") (pin "66") (pinfunction "PE7/T1OUT/SEG22/P2.7_66") (pintype "passive"))
    )
    (net (code "109") (name "/PF0") (class "Default")
      (node (ref "P17") (pin "27") (pinfunction "SEG23_27") (pintype "passive"))
      (node (ref "P3") (pin "9") (pinfunction "9_9") (pintype "passive"))
      (node (ref "T2") (pin "1") (pinfunction "1_1") (pintype "passive"))
      (node (ref "U1") (pin "67") (pinfunction "PF0/T2OUT/SEG23(SVS1)_67") (pintype "passive"))
    )
    (net (code "110") (name "/PF1") (class "Default")
      (node (ref "P18") (pin "7") (pinfunction "7_7") (pintype "passive"))
      (node (ref "P28") (pin "2") (pinfunction "2_2") (pintype "passive"))
      (node (ref "P3") (pin "8") (pinfunction "8_8") (pintype "passive"))
      (node (ref "T1") (pin "1") (pinfunction "1_1") (pintype "passive"))
      (node (ref "U1") (pin "68") (pinfunction "PF1/SVS0(VDISP1)/RXD1/IT0IN_68") (pintype "passive"))
    )
    (net (code "111") (name "/PF2") (class "Default")
      (node (ref "P18") (pin "5") (pinfunction "5_5") (pintype "passive"))
      (node (ref "P28") (pin "4") (pinfunction "4_4") (pintype "passive"))
      (node (ref "P3") (pin "7") (pinfunction "7_7") (pintype "passive"))
      (node (ref "U1") (pin "69") (pinfunction "PF2/VDISP2/TXD1/IT1IN_69") (pintype "passive"))
    )
    (net (code "112") (name "/PF3") (class "Default")
      (node (ref "P12") (pin "1") (pinfunction "1_1") (pintype "passive"))
      (node (ref "P18") (pin "3") (pinfunction "3_3") (pintype "passive"))
      (node (ref "P3") (pin "6") (pinfunction "6_6") (pintype "passive"))
      (node (ref "U1") (pin "70") (pinfunction "PF3/VDISP3/RXD0/IT2IN_70") (pintype "passive"))
    )
    (net (code "113") (name "/PF4") (class "Default")
      (node (ref "P12") (pin "3") (pinfunction "3_3") (pintype "passive"))
      (node (ref "P18") (pin "1") (pinfunction "1_1") (pintype "passive"))
      (node (ref "P3") (pin "5") (pinfunction "5_5") (pintype "passive"))
      (node (ref "T17") (pin "1") (pinfunction "1_1") (pintype "passive"))
      (node (ref "U1") (pin "71") (pinfunction "PF4/VCIN1/TXD0/IT2CKOUT_71") (pintype "passive"))
    )
    (net (code "114") (name "/PF6") (class "Default")
      (node (ref "P3") (pin "3") (pinfunction "3_3") (pintype "passive"))
      (node (ref "T5") (pin "1") (pinfunction "1_1") (pintype "passive"))
      (node (ref "U1") (pin "73") (pinfunction "PF6/AN3(ANTST0)/WKUP3_73") (pintype "passive"))
    )
    (net (code "115") (name "/PG4") (class "Default")
      (node (ref "P4") (pin "5") (pinfunction "5_5") (pintype "passive"))
      (node (ref "T18") (pin "1") (pinfunction "1_1") (pintype "passive"))
      (node (ref "U1") (pin "99") (pinfunction "FOUT0/PCACAPT0/PG4_99") (pintype "passive"))
    )
    (net (code "116") (name "/PG5") (class "Default")
      (node (ref "P15") (pin "5") (pinfunction "5_5") (pintype "passive"))
      (node (ref "P4") (pin "4") (pinfunction "4_4") (pintype "passive"))
      (node (ref "U1") (pin "100") (pinfunction "PCACAPT1/RXD3/PG5_100") (pintype "passive"))
    )
    (net (code "117") (name "/PG6") (class "Default")
      (node (ref "P15") (pin "7") (pinfunction "7_7") (pintype "passive"))
      (node (ref "P4") (pin "3") (pinfunction "3_3") (pintype "passive"))
      (node (ref "U1") (pin "101") (pinfunction "PCACAPT2/TXD3/PG6_101") (pintype "passive"))
    )
    (net (code "118") (name "/PG7") (class "Default")
      (node (ref "P4") (pin "2") (pinfunction "2_2") (pintype "passive"))
      (node (ref "U1") (pin "102") (pinfunction "PCACOMP4/EXVREF/(VLED)/PG7_102") (pintype "passive"))
    )
    (net (code "119") (name "/PH0") (class "Default")
      (node (ref "P29") (pin "4") (pinfunction "4_4") (pintype "passive"))
      (node (ref "P4") (pin "11") (pinfunction "11_11") (pintype "passive"))
      (node (ref "U1") (pin "93") (pinfunction "(VESAM)/WKUP4/PH0_93") (pintype "passive"))
    )
    (net (code "120") (name "/PROGEN") (class "Default")
      (node (ref "J2") (pin "7") (pinfunction "7_7") (pintype "passive"))
      (node (ref "U7") (pin "75") (pinfunction "INPUT67/PROGEN(RESET)_75") (pintype "bidirectional"))
    )
    (net (code "121") (name "/REMAP0") (class "Default")
      (node (ref "P16") (pin "2") (pinfunction "2_2") (pintype "passive"))
      (node (ref "U7") (pin "1") (pinfunction "GPIO70/REMAP0/VLCD/V_ESAM/timer2clkout/SEG36_1") (pintype "bidirectional"))
    )
    (net (code "122") (name "/RESET") (class "Default")
      (node (ref "C1") (pin "1") (pinfunction "1_1") (pintype "passive"))
      (node (ref "J1") (pin "4") (pinfunction "4_4") (pintype "passive"))
      (node (ref "P4") (pin "10") (pinfunction "10_10") (pintype "passive"))
      (node (ref "P7") (pin "1") (pinfunction "1_1") (pintype "passive"))
      (node (ref "RESET") (pin "2") (pinfunction "2_2") (pintype "passive"))
      (node (ref "U1") (pin "94") (pinfunction "(RESET)/TEST_N_94") (pintype "passive"))
    )
    (net (code "123") (name "/SCAN_MODE") (class "Default")
      (node (ref "P2") (pin "1") (pinfunction "1_1") (pintype "passive"))
      (node (ref "U1") (pin "30") (pinfunction "SCAN_MODE_30") (pintype "passive"))
    )
    (net (code "124") (name "/SPI_CLK_flash") (class "Default")
      (node (ref "P20") (pin "8") (pinfunction "8_8") (pintype "passive"))
      (node (ref "U6") (pin "6") (pinfunction "CLK_6") (pintype "input"))
    )
    (net (code "125") (name "/SPI_CS_flash") (class "Default")
      (node (ref "P20") (pin "2") (pinfunction "2_2") (pintype "passive"))
      (node (ref "U6") (pin "1") (pinfunction "CS_N_1") (pintype "input"))
    )
    (net (code "126") (name "/TCK") (class "Default")
      (node (ref "J2") (pin "5") (pinfunction "5_5") (pintype "passive"))
      (node (ref "U7") (pin "78") (pinfunction "GPIO64/TCK/TCLK/SCAN_CLK_78") (pintype "bidirectional"))
    )
    (net (code "127") (name "/TDI") (class "Default")
      (node (ref "J2") (pin "1") (pinfunction "1_1") (pintype "passive"))
      (node (ref "U7") (pin "76") (pinfunction "GPIO62/RXD1/TDI/STROBE/SCAN_RSTN_76") (pintype "bidirectional"))
    )
    (net (code "128") (name "/TDO") (class "Default")
      (node (ref "J2") (pin "3") (pinfunction "3_3") (pintype "passive"))
      (node (ref "U7") (pin "80") (pinfunction "GPIO66/TDO/TDIO_80") (pintype "bidirectional"))
    )
    (net (code "129") (name "/TIM_IN") (class "Default")
      (node (ref "J1") (pin "6") (pinfunction "6_6") (pintype "passive"))
      (node (ref "P10") (pin "2") (pinfunction "2_2") (pintype "passive"))
    )
    (net (code "130") (name "/TMS") (class "Default")
      (node (ref "J2") (pin "10") (pinfunction "10_10") (pintype "passive"))
      (node (ref "U7") (pin "77") (pinfunction "GPIO63/TXD1/TMS_77") (pintype "bidirectional"))
    )
    (net (code "131") (name "/VBAT") (class "Default")
      (node (ref "C17") (pin "2") (pinfunction "2_2") (pintype "passive"))
      (node (ref "P24") (pin "2") (pinfunction "2_2") (pintype "passive"))
      (node (ref "U7") (pin "63") (pinfunction "VBAT_63") (pintype "passive"))
    )
    (net (code "132") (name "/VDD15") (class "Default")
      (node (ref "P4") (pin "13") (pinfunction "13_13") (pintype "passive"))
      (node (ref "U1") (pin "90") (pinfunction "VDD15_90") (pintype "passive"))
    )
    (net (code "133") (name "/VDD15_318") (class "Default")
      (node (ref "C21") (pin "2") (pinfunction "2_2") (pintype "passive"))
      (node (ref "U7") (pin "67") (pinfunction "VDD15_67") (pintype "passive"))
    )
    (net (code "134") (name "/VDDP") (class "Default")
      (node (ref "P24") (pin "4") (pinfunction "4_4") (pintype "passive"))
      (node (ref "P4") (pin "17") (pinfunction "17_17") (pintype "passive"))
      (node (ref "U1") (pin "85") (pinfunction "VDDP_85") (pintype "passive"))
      (node (ref "Z1") (pin "2") (pinfunction "2_2") (pintype "passive"))
    )
    (net (code "135") (name "/VDDP_318") (class "Default")
      (node (ref "C20") (pin "2") (pinfunction "2_2") (pintype "passive"))
      (node (ref "U7") (pin "66") (pinfunction "VDDP_66") (pintype "passive"))
    )
    (net (code "136") (name "/VPP") (class "Default")
      (node (ref "P2") (pin "4") (pinfunction "4_4") (pintype "passive"))
      (node (ref "U1") (pin "33") (pinfunction "VPP_33") (pintype "passive"))
    )
    (net (code "137") (name "/VSS") (class "Default")
      (node (ref "P4") (pin "14") (pinfunction "14_14") (pintype "passive"))
      (node (ref "U1") (pin "88") (pinfunction "VSS_88") (pintype "passive"))
      (node (ref "Z2") (pin "1") (pinfunction "1_1") (pintype "passive"))
    )
    (net (code "138") (name "/V_7816") (class "Default")
      (node (ref "P29") (pin "1") (pinfunction "1_1") (pintype "passive"))
      (node (ref "P29") (pin "3") (pinfunction "3_3") (pintype "passive"))
      (node (ref "P30") (pin "19") (pinfunction "19_19") (pintype "passive"))
      (node (ref "P30") (pin "20") (pinfunction "20_20") (pintype "passive"))
    )
    (net (code "139") (name "/XTALIN_1") (class "Default")
      (node (ref "FDET") (pin "2") (pinfunction "2_2") (pintype "passive"))
      (node (ref "P3") (pin "2") (pinfunction "2_2") (pintype "passive"))
      (node (ref "U1") (pin "82") (pinfunction "XTALIN_82") (pintype "passive"))
    )
    (net (code "140") (name "/XTALIN_318") (class "Default")
      (node (ref "U7") (pin "60") (pinfunction "pad_xtalin_60") (pintype "passive"))
      (node (ref "XTAL1") (pin "1") (pinfunction "1_1") (pintype "passive"))
    )
    (net (code "141") (name "/XTALOUT_1") (class "Default")
      (node (ref "P3") (pin "1") (pinfunction "1_1") (pintype "passive"))
      (node (ref "U1") (pin "84") (pinfunction "XTALOUT_84") (pintype "passive"))
    )
    (net (code "142") (name "/XTALOUT_318") (class "Default")
      (node (ref "U7") (pin "61") (pinfunction "pad_xtalout_61") (pintype "passive"))
      (node (ref "XTAL1") (pin "2") (pinfunction "2_2") (pintype "passive"))
    )
    (net (code "143") (name "/charge") (class "Default")
      (node (ref "U17") (pin "1") (pinfunction "IN1_1") (pintype "passive"))
      (node (ref "U7") (pin "19") (pinfunction "GPIO16/SCL/P06_19") (pintype "bidirectional"))
    )
    (net (code "144") (name "/discharge") (class "Default")
      (node (ref "U17") (pin "16") (pinfunction "IN2_16") (pintype "passive"))
      (node (ref "U7") (pin "20") (pinfunction "GPIO17/SDA/PODR/P07_20") (pintype "bidirectional"))
    )
    (net (code "145") (name "/pad_cpll") (class "Default")
      (node (ref "C18") (pin "2") (pinfunction "2_2") (pintype "passive"))
      (node (ref "U7") (pin "68") (pinfunction "pad_cpll_68") (pintype "passive"))
    )
    (net (code "146") (name "AGND") (class "Default")
      (node (ref "C25") (pin "1") (pinfunction "1_1") (pintype "passive"))
      (node (ref "C26") (pin "1") (pinfunction "1_1") (pintype "passive"))
      (node (ref "C27") (pin "1") (pinfunction "1_1") (pintype "passive"))
      (node (ref "C28") (pin "2") (pintype "passive"))
      (node (ref "C30") (pin "2") (pinfunction "2_2") (pintype "passive"))
      (node (ref "C41") (pin "2") (pinfunction "2_2") (pintype "passive"))
      (node (ref "D7") (pin "1") (pinfunction "A_1") (pintype "passive"))
      (node (ref "R21") (pin "2") (pinfunction "2_2") (pintype "passive"))
      (node (ref "U17") (pin "5") (pinfunction "GND_5") (pintype "passive"))
      (node (ref "Z3") (pin "1") (pinfunction "1_1") (pintype "passive"))
    )
    (net (code "147") (name "GND") (class "Default")
      (node (ref "318UART0") (pin "10") (pinfunction "MH1_10") (pintype "passive"))
      (node (ref "318UART0") (pin "11") (pinfunction "MH2_11") (pintype "passive"))
      (node (ref "318UART0") (pin "5") (pinfunction "5_5") (pintype "passive"))
      (node (ref "318UART1") (pin "10") (pinfunction "MH1_10") (pintype "passive"))
      (node (ref "318UART1") (pin "11") (pinfunction "MH2_11") (pintype "passive"))
      (node (ref "318UART1") (pin "5") (pinfunction "5_5") (pintype "passive"))
      (node (ref "375UART0") (pin "10") (pinfunction "MH1_10") (pintype "passive"))
      (node (ref "375UART0") (pin "11") (pinfunction "MH2_11") (pintype "passive"))
      (node (ref "375UART0") (pin "5") (pinfunction "5_5") (pintype "passive"))
      (node (ref "375UART1") (pin "10") (pinfunction "MH1_10") (pintype "passive"))
      (node (ref "375UART1") (pin "11") (pinfunction "MH2_11") (pintype "passive"))
      (node (ref "375UART1") (pin "5") (pinfunction "5_5") (pintype "passive"))
      (node (ref "375UART2") (pin "10") (pinfunction "MH1_10") (pintype "passive"))
      (node (ref "375UART2") (pin "11") (pinfunction "MH2_11") (pintype "passive"))
      (node (ref "375UART2") (pin "5") (pinfunction "5_5") (pintype "passive"))
      (node (ref "375UART3") (pin "10") (pinfunction "MH1_10") (pintype "passive"))
      (node (ref "375UART3") (pin "11") (pinfunction "MH2_11") (pintype "passive"))
      (node (ref "375UART3") (pin "5") (pinfunction "5_5") (pintype "passive"))
      (node (ref "C1") (pin "2") (pinfunction "2_2") (pintype "passive"))
      (node (ref "C10") (pin "1") (pintype "passive"))
      (node (ref "C11") (pin "2") (pintype "passive"))
      (node (ref "C12") (pin "2") (pinfunction "2_2") (pintype "passive"))
      (node (ref "C13") (pin "2") (pinfunction "2_2") (pintype "passive"))
      (node (ref "C14") (pin "2") (pinfunction "2_2") (pintype "passive"))
      (node (ref "C16") (pin "2") (pinfunction "2_2") (pintype "passive"))
      (node (ref "C17") (pin "1") (pinfunction "1_1") (pintype "passive"))
      (node (ref "C18") (pin "1") (pinfunction "1_1") (pintype "passive"))
      (node (ref "C19") (pin "1") (pinfunction "1_1") (pintype "passive"))
      (node (ref "C20") (pin "1") (pinfunction "1_1") (pintype "passive"))
      (node (ref "C21") (pin "1") (pinfunction "1_1") (pintype "passive"))
      (node (ref "C22") (pin "2") (pinfunction "2_2") (pintype "passive"))
      (node (ref "C23") (pin "2") (pinfunction "2_2") (pintype "passive"))
      (node (ref "C24") (pin "1") (pinfunction "1_1") (pintype "passive"))
      (node (ref "C35") (pin "2") (pinfunction "2_2") (pintype "passive"))
      (node (ref "C36") (pin "2") (pintype "passive"))
      (node (ref "C37") (pin "2") (pinfunction "2_2") (pintype "passive"))
      (node (ref "C38") (pin "2") (pintype "passive"))
      (node (ref "C39") (pin "2") (pinfunction "2_2") (pintype "passive"))
      (node (ref "C40") (pin "1") (pinfunction "1_1") (pintype "passive"))
      (node (ref "C45") (pin "1") (pintype "passive"))
      (node (ref "C46") (pin "1") (pintype "passive"))
      (node (ref "C5") (pin "1") (pintype "passive"))
      (node (ref "C50") (pin "2") (pinfunction "2_2") (pintype "passive"))
      (node (ref "C51") (pin "2") (pinfunction "2_2") (pintype "passive"))
      (node (ref "C52") (pin "2") (pinfunction "2_2") (pintype "passive"))
      (node (ref "C53") (pin "2") (pinfunction "2_2") (pintype "passive"))
      (node (ref "C6") (pin "2") (pintype "passive"))
      (node (ref "D8") (pin "K") (pinfunction "2_K") (pintype "passive"))
      (node (ref "D9") (pin "K") (pinfunction "2_K") (pintype "passive"))
      (node (ref "FDET") (pin "1") (pinfunction "1_1") (pintype "passive"))
      (node (ref "J1") (pin "10") (pinfunction "10_10") (pintype "passive"))
      (node (ref "J1") (pin "3") (pinfunction "3_3") (pintype "passive"))
      (node (ref "J1") (pin "8") (pinfunction "8_8") (pintype "passive"))
      (node (ref "J10") (pin "1") (pinfunction "1_1") (pintype "passive"))
      (node (ref "J10") (pin "2") (pinfunction "2_2") (pintype "passive"))
      (node (ref "J10") (pin "3") (pinfunction "3_3") (pintype "passive"))
      (node (ref "J10") (pin "4") (pinfunction "4_4") (pintype "passive"))
      (node (ref "J10") (pin "5") (pinfunction "5_5") (pintype "passive"))
      (node (ref "J10") (pin "6") (pinfunction "6_6") (pintype "passive"))
      (node (ref "J2") (pin "2") (pinfunction "2_2") (pintype "passive"))
      (node (ref "J2") (pin "4") (pinfunction "4_4") (pintype "passive"))
      (node (ref "J2") (pin "6") (pinfunction "6_6") (pintype "passive"))
      (node (ref "J7") (pin "1") (pinfunction "1_1") (pintype "passive"))
      (node (ref "J7") (pin "2") (pinfunction "2_2") (pintype "passive"))
      (node (ref "J7") (pin "3") (pinfunction "3_3") (pintype "passive"))
      (node (ref "J7") (pin "4") (pinfunction "4_4") (pintype "passive"))
      (node (ref "J7") (pin "5") (pinfunction "5_5") (pintype "passive"))
      (node (ref "J7") (pin "6") (pinfunction "6_6") (pintype "passive"))
      (node (ref "J8") (pin "1") (pinfunction "1_1") (pintype "passive"))
      (node (ref "J8") (pin "2") (pinfunction "2_2") (pintype "passive"))
      (node (ref "J8") (pin "3") (pinfunction "3_3") (pintype "passive"))
      (node (ref "J8") (pin "4") (pinfunction "4_4") (pintype "passive"))
      (node (ref "J8") (pin "5") (pinfunction "5_5") (pintype "passive"))
      (node (ref "J8") (pin "6") (pinfunction "6_6") (pintype "passive"))
      (node (ref "J9") (pin "1") (pinfunction "1_1") (pintype "passive"))
      (node (ref "J9") (pin "2") (pinfunction "2_2") (pintype "passive"))
      (node (ref "J9") (pin "3") (pinfunction "3_3") (pintype "passive"))
      (node (ref "J9") (pin "4") (pinfunction "4_4") (pintype "passive"))
      (node (ref "J9") (pin "5") (pinfunction "5_5") (pintype "passive"))
      (node (ref "J9") (pin "6") (pinfunction "6_6") (pintype "passive"))
      (node (ref "K1") (pin "2") (pinfunction "2_2") (pintype "passive"))
      (node (ref "K2") (pin "2") (pinfunction "2_2") (pintype "passive"))
      (node (ref "K3") (pin "2") (pinfunction "2_2") (pintype "passive"))
      (node (ref "K4") (pin "2") (pinfunction "2_2") (pintype "passive"))
      (node (ref "NEG") (pin "1") (pinfunction "1_1") (pintype "passive"))
      (node (ref "P21") (pin "2") (pintype "passive"))
      (node (ref "P21") (pin "3") (pintype "passive"))
      (node (ref "P22") (pin "2") (pintype "passive"))
      (node (ref "P22") (pin "3") (pintype "passive"))
      (node (ref "P23") (pin "2") (pintype "passive"))
      (node (ref "P23") (pin "3") (pintype "passive"))
      (node (ref "P30") (pin "1") (pinfunction "1_1") (pintype "passive"))
      (node (ref "P30") (pin "2") (pinfunction "2_2") (pintype "passive"))
      (node (ref "P31") (pin "3") (pinfunction "3_3") (pintype "passive"))
      (node (ref "P4") (pin "15") (pinfunction "15_15") (pintype "passive"))
      (node (ref "P5") (pin "3") (pinfunction "3_3") (pintype "passive"))
      (node (ref "P6") (pin "3") (pinfunction "3_3") (pintype "passive"))
      (node (ref "P7") (pin "2") (pinfunction "2_2") (pintype "passive"))
      (node (ref "R37") (pin "1") (pinfunction "1_1") (pintype "passive"))
      (node (ref "R44") (pin "1") (pinfunction "1_1") (pintype "passive"))
      (node (ref "R45") (pin "1") (pinfunction "1_1") (pintype "passive"))
      (node (ref "R46") (pin "1") (pinfunction "1_1") (pintype "passive"))
      (node (ref "R47") (pin "1") (pinfunction "1_1") (pintype "passive"))
      (node (ref "R5") (pin "2") (pinfunction "2_2") (pintype "passive"))
      (node (ref "R6") (pin "2") (pinfunction "2_2") (pintype "passive"))
      (node (ref "R7") (pin "2") (pinfunction "2_2") (pintype "passive"))
      (node (ref "R8") (pin "2") (pinfunction "2_2") (pintype "passive"))
      (node (ref "R9") (pin "2") (pinfunction "2_2") (pintype "passive"))
      (node (ref "RESET") (pin "1") (pinfunction "1_1") (pintype "passive"))
      (node (ref "U1") (pin "87") (pinfunction "GND_87") (pintype "passive"))
      (node (ref "U2") (pin "1") (pinfunction "A0_1") (pintype "passive"))
      (node (ref "U2") (pin "2") (pinfunction "A1_2") (pintype "passive"))
      (node (ref "U2") (pin "3") (pinfunction "A2_3") (pintype "passive"))
      (node (ref "U2") (pin "4") (pinfunction "GND_4") (pintype "passive"))
      (node (ref "U2") (pin "7") (pinfunction "WP_7") (pintype "passive"))
      (node (ref "U3") (pin "15") (pinfunction "GND_15") (pintype "passive"))
      (node (ref "U4") (pin "15") (pinfunction "GND_15") (pintype "passive"))
      (node (ref "U5") (pin "15") (pinfunction "GND_15") (pintype "passive"))
      (node (ref "U6") (pin "4") (pinfunction "GND_4") (pintype "power_in"))
      (node (ref "U7") (pin "64") (pinfunction "gnd_64") (pintype "passive"))
      (node (ref "Z2") (pin "2") (pinfunction "2_2") (pintype "passive"))
      (node (ref "Z3") (pin "2") (pinfunction "2_2") (pintype "passive"))
    )
    (net (code "148") (name "Net-(318UART1-Pad4)") (class "Default")
      (node (ref "318UART1") (pin "4") (pinfunction "4_4") (pintype "passive"))
      (node (ref "S9") (pin "2") (pinfunction "2_2") (pintype "passive"))
    )
    (net (code "149") (name "Net-(375UART2-Pad4)") (class "Default")
      (node (ref "375UART2") (pin "4") (pinfunction "4_4") (pintype "passive"))
      (node (ref "S8") (pin "2") (pinfunction "2_2") (pintype "passive"))
    )
    (net (code "150") (name "Net-(ADC VIN-Pad1)") (class "Default")
      (node (ref "ADC VIN") (pin "1") (pinfunction "1_1") (pintype "passive"))
      (node (ref "C30") (pin "1") (pinfunction "1_1") (pintype "passive"))
      (node (ref "R22") (pin "1") (pinfunction "1_1") (pintype "passive"))
      (node (ref "S2") (pin "2") (pinfunction "2_2") (pintype "passive"))
      (node (ref "S3") (pin "2") (pinfunction "2_2") (pintype "passive"))
      (node (ref "S4") (pin "2") (pinfunction "2_2") (pintype "passive"))
    )
    (net (code "151") (name "Net-(C12-Pad1)") (class "Default")
      (node (ref "C12") (pin "1") (pinfunction "1_1") (pintype "passive"))
      (node (ref "P18") (pin "4") (pinfunction "4_4") (pintype "passive"))
    )
    (net (code "152") (name "Net-(C13-Pad1)") (class "Default")
      (node (ref "C13") (pin "1") (pinfunction "1_1") (pintype "passive"))
      (node (ref "P18") (pin "6") (pinfunction "6_6") (pintype "passive"))
    )
    (net (code "153") (name "Net-(C14-Pad1)") (class "Default")
      (node (ref "C14") (pin "1") (pinfunction "1_1") (pintype "passive"))
      (node (ref "P18") (pin "8") (pinfunction "8_8") (pintype "passive"))
    )
    (net (code "154") (name "Net-(C15-Pad1)") (class "Default")
      (node (ref "C15") (pin "1") (pinfunction "1_1") (pintype "passive"))
      (node (ref "P18") (pin "2") (pinfunction "2_2") (pintype "passive"))
    )
    (net (code "155") (name "Net-(D1-1)") (class "Default")
      (node (ref "D1") (pin "A") (pinfunction "1_A") (pintype "passive"))
      (node (ref "R23") (pin "2") (pinfunction "2_2") (pintype "passive"))
    )
    (net (code "156") (name "Net-(D2-1)") (class "Default")
      (node (ref "D2") (pin "A") (pinfunction "1_A") (pintype "passive"))
      (node (ref "R24") (pin "2") (pinfunction "2_2") (pintype "passive"))
    )
    (net (code "157") (name "Net-(D3-1)") (class "Default")
      (node (ref "D3") (pin "A") (pinfunction "1_A") (pintype "passive"))
      (node (ref "R25") (pin "2") (pinfunction "2_2") (pintype "passive"))
    )
    (net (code "158") (name "Net-(D4-1)") (class "Default")
      (node (ref "D4") (pin "A") (pinfunction "1_A") (pintype "passive"))
      (node (ref "R26") (pin "2") (pinfunction "2_2") (pintype "passive"))
    )
    (net (code "159") (name "Net-(D6-A)") (class "Default")
      (node (ref "C29") (pin "1") (pintype "passive"))
      (node (ref "D6") (pin "1") (pinfunction "A_1") (pintype "passive"))
      (node (ref "D7") (pin "2") (pinfunction "K_2") (pintype "passive"))
      (node (ref "R22") (pin "2") (pinfunction "2_2") (pintype "passive"))
      (node (ref "U8") (pin "6") (pinfunction "OUT_6") (pintype "passive"))
      (node (ref "integrator out") (pin "1") (pinfunction "1_1") (pintype "passive"))
    )
    (net (code "160") (name "Net-(D8-1)") (class "Default")
      (node (ref "D8") (pin "A") (pinfunction "1_A") (pintype "passive"))
      (node (ref "R35") (pin "2") (pinfunction "2_2") (pintype "passive"))
    )
    (net (code "161") (name "Net-(D9-1)") (class "Default")
      (node (ref "D9") (pin "A") (pinfunction "1_A") (pintype "passive"))
      (node (ref "R36") (pin "2") (pinfunction "2_2") (pintype "passive"))
    )
    (net (code "162") (name "Net-(D10-1)") (class "Default")
      (node (ref "D10") (pin "A") (pinfunction "1_A") (pintype "passive"))
      (node (ref "R37") (pin "2") (pinfunction "2_2") (pintype "passive"))
    )
    (net (code "163") (name "Net-(J1-Pad12)") (class "Default")
      (node (ref "J1") (pin "12") (pinfunction "12_12") (pintype "passive"))
      (node (ref "JP1") (pin "2") (pinfunction "2_2") (pintype "passive"))
    )
    (net (code "164") (name "Net-(P8-Pad1)") (class "Default")
      (node (ref "P8") (pin "1") (pinfunction "1_1") (pintype "passive"))
      (node (ref "R5") (pin "1") (pinfunction "1_1") (pintype "passive"))
    )
    (net (code "165") (name "Net-(P8-Pad3)") (class "Default")
      (node (ref "P8") (pin "3") (pinfunction "3_3") (pintype "passive"))
      (node (ref "R6") (pin "1") (pinfunction "1_1") (pintype "passive"))
    )
    (net (code "166") (name "Net-(P8-Pad5)") (class "Default")
      (node (ref "P8") (pin "5") (pinfunction "5_5") (pintype "passive"))
      (node (ref "R7") (pin "1") (pinfunction "1_1") (pintype "passive"))
    )
    (net (code "167") (name "Net-(P8-Pad7)") (class "Default")
      (node (ref "P8") (pin "7") (pinfunction "7_7") (pintype "passive"))
      (node (ref "R8") (pin "1") (pinfunction "1_1") (pintype "passive"))
    )
    (net (code "168") (name "Net-(P8-Pad9)") (class "Default")
      (node (ref "P8") (pin "9") (pinfunction "9_9") (pintype "passive"))
      (node (ref "R9") (pin "1") (pinfunction "1_1") (pintype "passive"))
    )
    (net (code "169") (name "Net-(P21-Pad1)") (class "Default")
      (node (ref "P21") (pin "1") (pintype "passive"))
      (node (ref "S5") (pin "2") (pinfunction "2_2") (pintype "passive"))
    )
    (net (code "170") (name "Net-(P22-Pad1)") (class "Default")
      (node (ref "P22") (pin "1") (pintype "passive"))
      (node (ref "S6") (pin "2") (pinfunction "2_2") (pintype "passive"))
    )
    (net (code "171") (name "Net-(P23-Pad1)") (class "Default")
      (node (ref "P23") (pin "1") (pintype "passive"))
      (node (ref "S7") (pin "2") (pinfunction "2_2") (pintype "passive"))
    )
    (net (code "172") (name "Net-(R10-Pad1)") (class "Default")
      (node (ref "R10") (pin "1") (pinfunction "1_1") (pintype "passive"))
      (node (ref "R11") (pin "2") (pinfunction "2_2") (pintype "passive"))
    )
    (net (code "173") (name "Net-(R11-Pad1)") (class "Default")
      (node (ref "R11") (pin "1") (pinfunction "1_1") (pintype "passive"))
      (node (ref "R12") (pin "2") (pinfunction "2_2") (pintype "passive"))
    )
    (net (code "174") (name "Net-(R12-Pad1)") (class "Default")
      (node (ref "R12") (pin "1") (pinfunction "1_1") (pintype "passive"))
      (node (ref "R13") (pin "1") (pinfunction "1_1") (pintype "passive"))
    )
    (net (code "175") (name "Net-(R13-Pad2)") (class "Default")
      (node (ref "R13") (pin "2") (pinfunction "2_2") (pintype "passive"))
      (node (ref "R14") (pin "1") (pinfunction "1_1") (pintype "passive"))
    )
    (net (code "176") (name "Net-(R15-Pad2)") (class "Default")
      (node (ref "R15") (pin "2") (pinfunction "2_2") (pintype "passive"))
      (node (ref "R16") (pin "1") (pinfunction "1_1") (pintype "passive"))
    )
    (net (code "177") (name "Net-(R16-Pad2)") (class "Default")
      (node (ref "R16") (pin "2") (pinfunction "2_2") (pintype "passive"))
      (node (ref "R17") (pin "1") (pinfunction "1_1") (pintype "passive"))
    )
    (net (code "178") (name "Net-(R17-Pad2)") (class "Default")
      (node (ref "R17") (pin "2") (pinfunction "2_2") (pintype "passive"))
      (node (ref "R18") (pin "1") (pinfunction "1_1") (pintype "passive"))
    )
    (net (code "179") (name "Net-(R18-Pad2)") (class "Default")
      (node (ref "R18") (pin "2") (pinfunction "2_2") (pintype "passive"))
      (node (ref "R19") (pin "1") (pinfunction "1_1") (pintype "passive"))
    )
    (net (code "180") (name "Net-(U2-SCL)") (class "Default")
      (node (ref "R28") (pin "2") (pinfunction "2_2") (pintype "passive"))
      (node (ref "R29") (pin "1") (pinfunction "1_1") (pintype "passive"))
      (node (ref "U2") (pin "6") (pinfunction "SCL_6") (pintype "passive"))
    )
    (net (code "181") (name "Net-(U2-SDA)") (class "Default")
      (node (ref "R27") (pin "2") (pinfunction "2_2") (pintype "passive"))
      (node (ref "R30") (pin "2") (pinfunction "2_2") (pintype "passive"))
      (node (ref "U2") (pin "5") (pinfunction "SDA_5") (pintype "passive"))
    )
    (net (code "182") (name "Net-(U3-C1+)") (class "Default")
      (node (ref "C8") (pin "2") (pintype "passive"))
      (node (ref "U3") (pin "1") (pinfunction "C1+_1") (pintype "passive"))
    )
    (net (code "183") (name "Net-(U3-C1-)") (class "Default")
      (node (ref "C8") (pin "1") (pintype "passive"))
      (node (ref "U3") (pin "3") (pinfunction "C1-_3") (pintype "passive"))
    )
    (net (code "184") (name "Net-(U3-C2+)") (class "Default")
      (node (ref "C9") (pin "1") (pintype "passive"))
      (node (ref "U3") (pin "4") (pinfunction "C2+_4") (pintype "passive"))
    )
    (net (code "185") (name "Net-(U3-C2-)") (class "Default")
      (node (ref "C9") (pin "2") (pintype "passive"))
      (node (ref "U3") (pin "5") (pinfunction "C2-_5") (pintype "passive"))
    )
    (net (code "186") (name "Net-(U3-R1IN)") (class "Default")
      (node (ref "375UART3") (pin "2") (pinfunction "2_2") (pintype "passive"))
      (node (ref "U3") (pin "13") (pinfunction "R1IN_13") (pintype "passive"))
    )
    (net (code "187") (name "Net-(U3-R2IN)") (class "Default")
      (node (ref "375UART1") (pin "2") (pinfunction "2_2") (pintype "passive"))
      (node (ref "U3") (pin "8") (pinfunction "R2IN_8") (pintype "passive"))
    )
    (net (code "188") (name "Net-(U3-T1OUT)") (class "Default")
      (node (ref "375UART3") (pin "3") (pinfunction "3_3") (pintype "passive"))
      (node (ref "U3") (pin "14") (pinfunction "T1OUT_14") (pintype "passive"))
    )
    (net (code "189") (name "Net-(U3-T2OUT)") (class "Default")
      (node (ref "375UART1") (pin "3") (pinfunction "3_3") (pintype "passive"))
      (node (ref "U3") (pin "7") (pinfunction "T2OUT_7") (pintype "passive"))
    )
    (net (code "190") (name "Net-(U3-V+)") (class "Default")
      (node (ref "C7") (pin "1") (pintype "passive"))
      (node (ref "U3") (pin "2") (pinfunction "V+_2") (pintype "passive"))
    )
    (net (code "191") (name "Net-(U3-V-)") (class "Default")
      (node (ref "C11") (pin "1") (pintype "passive"))
      (node (ref "U3") (pin "6") (pinfunction "V-_6") (pintype "passive"))
    )
    (net (code "192") (name "Net-(U4-C1+)") (class "Default")
      (node (ref "C3") (pin "2") (pintype "passive"))
      (node (ref "U4") (pin "1") (pinfunction "C1+_1") (pintype "passive"))
    )
    (net (code "193") (name "Net-(U4-C1-)") (class "Default")
      (node (ref "C3") (pin "1") (pintype "passive"))
      (node (ref "U4") (pin "3") (pinfunction "C1-_3") (pintype "passive"))
    )
    (net (code "194") (name "Net-(U4-C2+)") (class "Default")
      (node (ref "C4") (pin "1") (pintype "passive"))
      (node (ref "U4") (pin "4") (pinfunction "C2+_4") (pintype "passive"))
    )
    (net (code "195") (name "Net-(U4-C2-)") (class "Default")
      (node (ref "C4") (pin "2") (pintype "passive"))
      (node (ref "U4") (pin "5") (pinfunction "C2-_5") (pintype "passive"))
    )
    (net (code "196") (name "Net-(U4-R1IN)") (class "Default")
      (node (ref "375UART2") (pin "2") (pinfunction "2_2") (pintype "passive"))
      (node (ref "U4") (pin "13") (pinfunction "R1IN_13") (pintype "passive"))
    )
    (net (code "197") (name "Net-(U4-R2IN)") (class "Default")
      (node (ref "375UART0") (pin "2") (pinfunction "2_2") (pintype "passive"))
      (node (ref "U4") (pin "8") (pinfunction "R2IN_8") (pintype "passive"))
    )
    (net (code "198") (name "Net-(U4-T1OUT)") (class "Default")
      (node (ref "375UART2") (pin "3") (pinfunction "3_3") (pintype "passive"))
      (node (ref "U4") (pin "14") (pinfunction "T1OUT_14") (pintype "passive"))
    )
    (net (code "199") (name "Net-(U4-T2OUT)") (class "Default")
      (node (ref "375UART0") (pin "3") (pinfunction "3_3") (pintype "passive"))
      (node (ref "U4") (pin "7") (pinfunction "T2OUT_7") (pintype "passive"))
    )
    (net (code "200") (name "Net-(U4-V+)") (class "Default")
      (node (ref "C2") (pin "1") (pintype "passive"))
      (node (ref "U4") (pin "2") (pinfunction "V+_2") (pintype "passive"))
    )
    (net (code "201") (name "Net-(U4-V-)") (class "Default")
      (node (ref "C6") (pin "1") (pintype "passive"))
      (node (ref "U4") (pin "6") (pinfunction "V-_6") (pintype "passive"))
    )
    (net (code "202") (name "Net-(U5-C1+)") (class "Default")
      (node (ref "C43") (pin "2") (pintype "passive"))
      (node (ref "U5") (pin "1") (pinfunction "C1+_1") (pintype "passive"))
    )
    (net (code "203") (name "Net-(U5-C1-)") (class "Default")
      (node (ref "C43") (pin "1") (pintype "passive"))
      (node (ref "U5") (pin "3") (pinfunction "C1-_3") (pintype "passive"))
    )
    (net (code "204") (name "Net-(U5-C2+)") (class "Default")
      (node (ref "C44") (pin "1") (pintype "passive"))
      (node (ref "U5") (pin "4") (pinfunction "C2+_4") (pintype "passive"))
    )
    (net (code "205") (name "Net-(U5-C2-)") (class "Default")
      (node (ref "C44") (pin "2") (pintype "passive"))
      (node (ref "U5") (pin "5") (pinfunction "C2-_5") (pintype "passive"))
    )
    (net (code "206") (name "Net-(U5-R1IN)") (class "Default")
      (node (ref "318UART1") (pin "2") (pinfunction "2_2") (pintype "passive"))
      (node (ref "U5") (pin "13") (pinfunction "R1IN_13") (pintype "passive"))
    )
    (net (code "207") (name "Net-(U5-R2IN)") (class "Default")
      (node (ref "318UART0") (pin "2") (pinfunction "2_2") (pintype "passive"))
      (node (ref "U5") (pin "8") (pinfunction "R2IN_8") (pintype "passive"))
    )
    (net (code "208") (name "Net-(U5-T1OUT)") (class "Default")
      (node (ref "318UART1") (pin "3") (pinfunction "3_3") (pintype "passive"))
      (node (ref "U5") (pin "14") (pinfunction "T1OUT_14") (pintype "passive"))
    )
    (net (code "209") (name "Net-(U5-T2OUT)") (class "Default")
      (node (ref "318UART0") (pin "3") (pinfunction "3_3") (pintype "passive"))
      (node (ref "U5") (pin "7") (pinfunction "T2OUT_7") (pintype "passive"))
    )
    (net (code "210") (name "Net-(U5-V+)") (class "Default")
      (node (ref "C42") (pin "1") (pintype "passive"))
      (node (ref "U5") (pin "2") (pinfunction "V+_2") (pintype "passive"))
    )
    (net (code "211") (name "Net-(U5-V-)") (class "Default")
      (node (ref "C46") (pin "2") (pintype "passive"))
      (node (ref "U5") (pin "6") (pinfunction "V-_6") (pintype "passive"))
    )
    (net (code "212") (name "Net-(U8-IN+)") (class "Default")
      (node (ref "C28") (pin "1") (pintype "passive"))
      (node (ref "R32") (pin "1") (pinfunction "1_1") (pintype "passive"))
      (node (ref "U8") (pin "3") (pinfunction "IN+_3") (pintype "passive"))
    )
    (net (code "213") (name "Net-(U8-IN-)") (class "Default")
      (node (ref "C29") (pin "2") (pintype "passive"))
      (node (ref "R21") (pin "1") (pinfunction "1_1") (pintype "passive"))
      (node (ref "U8") (pin "2") (pinfunction "IN-_2") (pintype "passive"))
    )
    (net (code "214") (name "Net-(V1-1)") (class "Default")
      (node (ref "R1") (pin "2") (pinfunction "2_2") (pintype "passive"))
      (node (ref "V1") (pin "A") (pinfunction "1_A") (pintype "passive"))
    )
    (net (code "215") (name "Net-(V2-1)") (class "Default")
      (node (ref "R2") (pin "2") (pinfunction "2_2") (pintype "passive"))
      (node (ref "V2") (pin "A") (pinfunction "1_A") (pintype "passive"))
    )
    (net (code "216") (name "Net-(V3-1)") (class "Default")
      (node (ref "R3") (pin "2") (pinfunction "2_2") (pintype "passive"))
      (node (ref "V3") (pin "A") (pinfunction "1_A") (pintype "passive"))
    )
    (net (code "217") (name "Net-(V4-1)") (class "Default")
      (node (ref "R4") (pin "2") (pinfunction "2_2") (pintype "passive"))
      (node (ref "V4") (pin "A") (pinfunction "1_A") (pintype "passive"))
    )
    (net (code "218") (name "VCC") (class "Default")
      (node (ref "C10") (pin "2") (pintype "passive"))
      (node (ref "C19") (pin "2") (pinfunction "2_2") (pintype "passive"))
      (node (ref "C2") (pin "2") (pintype "passive"))
      (node (ref "C24") (pin "2") (pinfunction "2_2") (pintype "passive"))
      (node (ref "C42") (pin "2") (pintype "passive"))
      (node (ref "C45") (pin "2") (pintype "passive"))
      (node (ref "C5") (pin "2") (pintype "passive"))
      (node (ref "C54") (pin "1") (pinfunction "1_1") (pintype "passive"))
      (node (ref "C55") (pin "1") (pinfunction "1_1") (pintype "passive"))
      (node (ref "C56") (pin "1") (pinfunction "1_1") (pintype "passive"))
      (node (ref "C57") (pin "1") (pinfunction "1_1") (pintype "passive"))
      (node (ref "C7") (pin "2") (pintype "passive"))
      (node (ref "K5") (pin "1") (pinfunction "1_1") (pintype "passive"))
      (node (ref "K6") (pin "1") (pinfunction "1_1") (pintype "passive"))
      (node (ref "K7") (pin "1") (pinfunction "1_1") (pintype "passive"))
      (node (ref "K8") (pin "1") (pinfunction "1_1") (pintype "passive"))
      (node (ref "P24") (pin "8") (pinfunction "8_8") (pintype "passive"))
      (node (ref "P29") (pin "2") (pinfunction "2_2") (pintype "passive"))
      (node (ref "P31") (pin "1") (pinfunction "1_1") (pintype "passive"))
      (node (ref "P5") (pin "1") (pinfunction "1_1") (pintype "passive"))
      (node (ref "P6") (pin "1") (pinfunction "1_1") (pintype "passive"))
      (node (ref "R1") (pin "1") (pinfunction "1_1") (pintype "passive"))
      (node (ref "R2") (pin "1") (pinfunction "1_1") (pintype "passive"))
      (node (ref "R23") (pin "1") (pinfunction "1_1") (pintype "passive"))
      (node (ref "R24") (pin "1") (pinfunction "1_1") (pintype "passive"))
      (node (ref "R25") (pin "1") (pinfunction "1_1") (pintype "passive"))
      (node (ref "R26") (pin "1") (pinfunction "1_1") (pintype "passive"))
      (node (ref "R27") (pin "1") (pinfunction "1_1") (pintype "passive"))
      (node (ref "R28") (pin "1") (pinfunction "1_1") (pintype "passive"))
      (node (ref "R3") (pin "1") (pinfunction "1_1") (pintype "passive"))
      (node (ref "R31") (pin "2") (pinfunction "2_2") (pintype "passive"))
      (node (ref "R4") (pin "1") (pinfunction "1_1") (pintype "passive"))
      (node (ref "R40") (pin "2") (pinfunction "2_2") (pintype "passive"))
      (node (ref "R41") (pin "2") (pinfunction "2_2") (pintype "passive"))
      (node (ref "R42") (pin "2") (pinfunction "2_2") (pintype "passive"))
      (node (ref "R43") (pin "2") (pinfunction "2_2") (pintype "passive"))
      (node (ref "S1") (pin "2") (pinfunction "2_2") (pintype "passive"))
      (node (ref "S10") (pin "1") (pinfunction "1_1") (pintype "passive"))
      (node (ref "S8") (pin "1") (pinfunction "1_1") (pintype "passive"))
      (node (ref "S9") (pin "1") (pinfunction "1_1") (pintype "passive"))
      (node (ref "U2") (pin "8") (pinfunction "VCC_8") (pintype "passive"))
      (node (ref "U3") (pin "16") (pinfunction "VCC_16") (pintype "passive"))
      (node (ref "U4") (pin "16") (pinfunction "VCC_16") (pintype "passive"))
      (node (ref "U5") (pin "16") (pinfunction "VCC_16") (pintype "passive"))
      (node (ref "U6") (pin "3") (pinfunction "WP_N_3") (pintype "input"))
      (node (ref "U6") (pin "7") (pinfunction "HOLD_N_7") (pintype "input"))
      (node (ref "U6") (pin "8") (pinfunction "VCC_8") (pintype "power_in"))
    )
    (net (code "219") (name "VCC5V") (class "Default")
      (node (ref "C37") (pin "1") (pinfunction "1_1") (pintype "passive"))
      (node (ref "C38") (pin "1") (pintype "passive"))
      (node (ref "J11") (pin "3") (pinfunction "3_3") (pintype "passive"))
      (node (ref "J11") (pin "4") (pinfunction "4_4") (pintype "passive"))
      (node (ref "P25") (pin "1") (pinfunction "1_1") (pintype "passive"))
      (node (ref "R36") (pin "1") (pinfunction "1_1") (pintype "passive"))
      (node (ref "S6") (pin "1") (pinfunction "1_1") (pintype "passive"))
      (node (ref "T7") (pin "1") (pinfunction "1_1") (pintype "passive"))
    )
    (net (code "220") (name "VCC_AD") (class "Default")
      (node (ref "C25") (pin "2") (pinfunction "2_2") (pintype "passive"))
      (node (ref "C27") (pin "2") (pinfunction "2_2") (pintype "passive"))
      (node (ref "D6") (pin "2") (pinfunction "K_2") (pintype "passive"))
      (node (ref "P25") (pin "2") (pinfunction "2_2") (pintype "passive"))
      (node (ref "R14") (pin "2") (pinfunction "2_2") (pintype "passive"))
      (node (ref "U17") (pin "13") (pinfunction "V+_13") (pintype "passive"))
      (node (ref "U8") (pin "7") (pinfunction "V+_7") (pintype "passive"))
    )
    (net (code "221") (name "VCC_DUT_IO") (class "Default")
      (node (ref "J2") (pin "11") (pinfunction "11_11") (pintype "passive"))
      (node (ref "S10") (pin "2") (pinfunction "2_2") (pintype "passive"))
    )
    (net (code "222") (name "VCC_DUT_IO_375") (class "Default")
      (node (ref "J1") (pin "7") (pinfunction "7_7") (pintype "passive"))
      (node (ref "S1") (pin "1") (pinfunction "1_1") (pintype "passive"))
      (node (ref "S11") (pin "2") (pinfunction "2_2") (pintype "passive"))
    )
    (net (code "223") (name "VDD5V") (class "Default")
      (node (ref "C35") (pin "1") (pinfunction "1_1") (pintype "passive"))
      (node (ref "C36") (pin "1") (pintype "passive"))
      (node (ref "J11") (pin "5") (pinfunction "5_5") (pintype "passive"))
      (node (ref "J11") (pin "6") (pinfunction "6_6") (pintype "passive"))
      (node (ref "P24") (pin "1") (pinfunction "1_1") (pintype "passive"))
      (node (ref "P24") (pin "3") (pinfunction "3_3") (pintype "passive"))
      (node (ref "P24") (pin "5") (pinfunction "5_5") (pintype "passive"))
      (node (ref "P24") (pin "7") (pinfunction "7_7") (pintype "passive"))
      (node (ref "R35") (pin "1") (pinfunction "1_1") (pintype "passive"))
      (node (ref "S5") (pin "1") (pinfunction "1_1") (pintype "passive"))
      (node (ref "T6") (pin "1") (pinfunction "1_1") (pintype "passive"))
    )
    (net (code "224") (name "VDD50") (class "Default")
      (node (ref "P24") (pin "6") (pinfunction "6_6") (pintype "passive"))
      (node (ref "P4") (pin "16") (pinfunction "16_16") (pintype "passive"))
      (node (ref "S11") (pin "1") (pinfunction "1_1") (pintype "passive"))
      (node (ref "U1") (pin "86") (pinfunction "VDD_86") (pintype "passive"))
      (node (ref "Z1") (pin "1") (pinfunction "1_1") (pintype "passive"))
    )
    (net (code "225") (name "unconnected-(318UART0-Pad1)") (class "Default")
      (node (ref "318UART0") (pin "1") (pinfunction "1_1") (pintype "passive+no_connect"))
    )
    (net (code "226") (name "unconnected-(318UART0-Pad4)") (class "Default")
      (node (ref "318UART0") (pin "4") (pinfunction "4_4") (pintype "passive+no_connect"))
    )
    (net (code "227") (name "unconnected-(318UART0-Pad6)") (class "Default")
      (node (ref "318UART0") (pin "6") (pinfunction "6_6") (pintype "passive+no_connect"))
    )
    (net (code "228") (name "unconnected-(318UART0-Pad7)") (class "Default")
      (node (ref "318UART0") (pin "7") (pinfunction "7_7") (pintype "passive+no_connect"))
    )
    (net (code "229") (name "unconnected-(318UART0-Pad8)") (class "Default")
      (node (ref "318UART0") (pin "8") (pinfunction "8_8") (pintype "passive+no_connect"))
    )
    (net (code "230") (name "unconnected-(318UART0-Pad9)") (class "Default")
      (node (ref "318UART0") (pin "9") (pinfunction "9_9") (pintype "passive+no_connect"))
    )
    (net (code "231") (name "unconnected-(318UART1-Pad1)") (class "Default")
      (node (ref "318UART1") (pin "1") (pinfunction "1_1") (pintype "passive+no_connect"))
    )
    (net (code "232") (name "unconnected-(318UART1-Pad6)") (class "Default")
      (node (ref "318UART1") (pin "6") (pinfunction "6_6") (pintype "passive+no_connect"))
    )
    (net (code "233") (name "unconnected-(318UART1-Pad7)") (class "Default")
      (node (ref "318UART1") (pin "7") (pinfunction "7_7") (pintype "passive+no_connect"))
    )
    (net (code "234") (name "unconnected-(318UART1-Pad8)") (class "Default")
      (node (ref "318UART1") (pin "8") (pinfunction "8_8") (pintype "passive+no_connect"))
    )
    (net (code "235") (name "unconnected-(318UART1-Pad9)") (class "Default")
      (node (ref "318UART1") (pin "9") (pinfunction "9_9") (pintype "passive+no_connect"))
    )
    (net (code "236") (name "unconnected-(375UART0-Pad1)") (class "Default")
      (node (ref "375UART0") (pin "1") (pinfunction "1_1") (pintype "passive+no_connect"))
    )
    (net (code "237") (name "unconnected-(375UART0-Pad4)") (class "Default")
      (node (ref "375UART0") (pin "4") (pinfunction "4_4") (pintype "passive+no_connect"))
    )
    (net (code "238") (name "unconnected-(375UART0-Pad6)") (class "Default")
      (node (ref "375UART0") (pin "6") (pinfunction "6_6") (pintype "passive+no_connect"))
    )
    (net (code "239") (name "unconnected-(375UART0-Pad7)") (class "Default")
      (node (ref "375UART0") (pin "7") (pinfunction "7_7") (pintype "passive+no_connect"))
    )
    (net (code "240") (name "unconnected-(375UART0-Pad8)") (class "Default")
      (node (ref "375UART0") (pin "8") (pinfunction "8_8") (pintype "passive+no_connect"))
    )
    (net (code "241") (name "unconnected-(375UART0-Pad9)") (class "Default")
      (node (ref "375UART0") (pin "9") (pinfunction "9_9") (pintype "passive+no_connect"))
    )
    (net (code "242") (name "unconnected-(375UART1-Pad1)") (class "Default")
      (node (ref "375UART1") (pin "1") (pinfunction "1_1") (pintype "passive+no_connect"))
    )
    (net (code "243") (name "unconnected-(375UART1-Pad4)") (class "Default")
      (node (ref "375UART1") (pin "4") (pinfunction "4_4") (pintype "passive+no_connect"))
    )
    (net (code "244") (name "unconnected-(375UART1-Pad6)") (class "Default")
      (node (ref "375UART1") (pin "6") (pinfunction "6_6") (pintype "passive+no_connect"))
    )
    (net (code "245") (name "unconnected-(375UART1-Pad7)") (class "Default")
      (node (ref "375UART1") (pin "7") (pinfunction "7_7") (pintype "passive+no_connect"))
    )
    (net (code "246") (name "unconnected-(375UART1-Pad8)") (class "Default")
      (node (ref "375UART1") (pin "8") (pinfunction "8_8") (pintype "passive+no_connect"))
    )
    (net (code "247") (name "unconnected-(375UART1-Pad9)") (class "Default")
      (node (ref "375UART1") (pin "9") (pinfunction "9_9") (pintype "passive+no_connect"))
    )
    (net (code "248") (name "unconnected-(375UART2-Pad1)") (class "Default")
      (node (ref "375UART2") (pin "1") (pinfunction "1_1") (pintype "passive+no_connect"))
    )
    (net (code "249") (name "unconnected-(375UART2-Pad6)") (class "Default")
      (node (ref "375UART2") (pin "6") (pinfunction "6_6") (pintype "passive+no_connect"))
    )
    (net (code "250") (name "unconnected-(375UART2-Pad7)") (class "Default")
      (node (ref "375UART2") (pin "7") (pinfunction "7_7") (pintype "passive+no_connect"))
    )
    (net (code "251") (name "unconnected-(375UART2-Pad8)") (class "Default")
      (node (ref "375UART2") (pin "8") (pinfunction "8_8") (pintype "passive+no_connect"))
    )
    (net (code "252") (name "unconnected-(375UART2-Pad9)") (class "Default")
      (node (ref "375UART2") (pin "9") (pinfunction "9_9") (pintype "passive+no_connect"))
    )
    (net (code "253") (name "unconnected-(375UART3-Pad1)") (class "Default")
      (node (ref "375UART3") (pin "1") (pinfunction "1_1") (pintype "passive+no_connect"))
    )
    (net (code "254") (name "unconnected-(375UART3-Pad4)") (class "Default")
      (node (ref "375UART3") (pin "4") (pinfunction "4_4") (pintype "passive+no_connect"))
    )
    (net (code "255") (name "unconnected-(375UART3-Pad6)") (class "Default")
      (node (ref "375UART3") (pin "6") (pinfunction "6_6") (pintype "passive+no_connect"))
    )
    (net (code "256") (name "unconnected-(375UART3-Pad7)") (class "Default")
      (node (ref "375UART3") (pin "7") (pinfunction "7_7") (pintype "passive+no_connect"))
    )
    (net (code "257") (name "unconnected-(375UART3-Pad8)") (class "Default")
      (node (ref "375UART3") (pin "8") (pinfunction "8_8") (pintype "passive+no_connect"))
    )
    (net (code "258") (name "unconnected-(375UART3-Pad9)") (class "Default")
      (node (ref "375UART3") (pin "9") (pinfunction "9_9") (pintype "passive+no_connect"))
    )
    (net (code "259") (name "unconnected-(J1-Pad1)") (class "Default")
      (node (ref "J1") (pin "1") (pinfunction "1_1") (pintype "passive+no_connect"))
    )
    (net (code "260") (name "unconnected-(J1-Pad2)") (class "Default")
      (node (ref "J1") (pin "2") (pinfunction "2_2") (pintype "passive+no_connect"))
    )
    (net (code "261") (name "unconnected-(J1-Pad14)") (class "Default")
      (node (ref "J1") (pin "14") (pinfunction "14_14") (pintype "passive+no_connect"))
    )
    (net (code "262") (name "unconnected-(J2-Pad8)") (class "Default")
      (node (ref "J2") (pin "8") (pinfunction "8_8") (pintype "passive+no_connect"))
    )
    (net (code "263") (name "unconnected-(J2-Pad9)") (class "Default")
      (node (ref "J2") (pin "9") (pinfunction "9_9") (pintype "passive+no_connect"))
    )
    (net (code "264") (name "unconnected-(J2-Pad12)") (class "Default")
      (node (ref "J2") (pin "12") (pinfunction "12_12") (pintype "passive+no_connect"))
    )
    (net (code "265") (name "unconnected-(J2-Pad13)") (class "Default")
      (node (ref "J2") (pin "13") (pinfunction "13_13") (pintype "passive+no_connect"))
    )
    (net (code "266") (name "unconnected-(J2-Pad14)") (class "Default")
      (node (ref "J2") (pin "14") (pinfunction "14_14") (pintype "passive+no_connect"))
    )
    (net (code "267") (name "unconnected-(P30-Pad3)") (class "Default")
      (node (ref "P30") (pin "3") (pinfunction "3_3") (pintype "passive"))
    )
    (net (code "268") (name "unconnected-(P30-Pad4)") (class "Default")
      (node (ref "P30") (pin "4") (pinfunction "4_4") (pintype "passive"))
    )
    (net (code "269") (name "unconnected-(P30-Pad5)") (class "Default")
      (node (ref "P30") (pin "5") (pinfunction "5_5") (pintype "passive"))
    )
    (net (code "270") (name "unconnected-(P30-Pad7)") (class "Default")
      (node (ref "P30") (pin "7") (pinfunction "7_7") (pintype "passive"))
    )
    (net (code "271") (name "unconnected-(P30-Pad9)") (class "Default")
      (node (ref "P30") (pin "9") (pinfunction "9_9") (pintype "passive"))
    )
    (net (code "272") (name "unconnected-(P30-Pad11)") (class "Default")
      (node (ref "P30") (pin "11") (pinfunction "11_11") (pintype "passive"))
    )
    (net (code "273") (name "unconnected-(P30-Pad13)") (class "Default")
      (node (ref "P30") (pin "13") (pinfunction "13_13") (pintype "passive"))
    )
    (net (code "274") (name "unconnected-(P30-Pad14)") (class "Default")
      (node (ref "P30") (pin "14") (pinfunction "14_14") (pintype "passive"))
    )
    (net (code "275") (name "unconnected-(P30-Pad15)") (class "Default")
      (node (ref "P30") (pin "15") (pinfunction "15_15") (pintype "passive"))
    )
    (net (code "276") (name "unconnected-(P30-Pad16)") (class "Default")
      (node (ref "P30") (pin "16") (pinfunction "16_16") (pintype "passive"))
    )
    (net (code "277") (name "unconnected-(P30-Pad17)") (class "Default")
      (node (ref "P30") (pin "17") (pinfunction "17_17") (pintype "passive"))
    )
    (net (code "278") (name "unconnected-(P30-Pad18)") (class "Default")
      (node (ref "P30") (pin "18") (pinfunction "18_18") (pintype "passive"))
    )
    (net (code "279") (name "unconnected-(S5-Pad3)") (class "Default")
      (node (ref "S5") (pin "3") (pinfunction "3_3") (pintype "passive+no_connect"))
    )
    (net (code "280") (name "unconnected-(S6-Pad3)") (class "Default")
      (node (ref "S6") (pin "3") (pinfunction "3_3") (pintype "passive+no_connect"))
    )
    (net (code "281") (name "unconnected-(S7-Pad3)") (class "Default")
      (node (ref "S7") (pin "3") (pinfunction "3_3") (pintype "passive+no_connect"))
    )
    (net (code "282") (name "unconnected-(U7-GPIO00{slash}COM0-Pad3)") (class "Default")
      (node (ref "U7") (pin "3") (pinfunction "GPIO00/COM0_3") (pintype "bidirectional"))
    )
    (net (code "283") (name "unconnected-(U7-GPIO01{slash}COM1-Pad4)") (class "Default")
      (node (ref "U7") (pin "4") (pinfunction "GPIO01/COM1_4") (pintype "bidirectional"))
    )
    (net (code "284") (name "unconnected-(U7-GPIO02{slash}COM2-Pad5)") (class "Default")
      (node (ref "U7") (pin "5") (pinfunction "GPIO02/COM2_5") (pintype "bidirectional"))
    )
    (net (code "285") (name "unconnected-(U7-GPIO03{slash}COM3-Pad6)") (class "Default")
      (node (ref "U7") (pin "6") (pinfunction "GPIO03/COM3_6") (pintype "bidirectional"))
    )
    (net (code "286") (name "unconnected-(U7-GPIO04{slash}SEG38{slash}COM4-Pad7)") (class "Default")
      (node (ref "U7") (pin "7") (pinfunction "GPIO04/SEG38/COM4_7") (pintype "bidirectional"))
    )
    (net (code "287") (name "unconnected-(U7-GPIO05{slash}SEG39{slash}COM5-Pad8)") (class "Default")
      (node (ref "U7") (pin "8") (pinfunction "GPIO05/SEG39/COM5_8") (pintype "bidirectional"))
    )
    (net (code "288") (name "unconnected-(U7-GPIO10{slash}INT0{slash}SEG2-Pad11)") (class "Default")
      (node (ref "U7") (pin "11") (pinfunction "GPIO10/INT0/SEG2_11") (pintype "bidirectional"))
    )
    (net (code "289") (name "unconnected-(U7-GPIO11{slash}INT1{slash}SEG3-Pad12)") (class "Default")
      (node (ref "U7") (pin "12") (pinfunction "GPIO11/INT1/SEG3_12") (pintype "bidirectional"))
    )
    (net (code "290") (name "unconnected-(U7-GPIO12{slash}RXD3{slash}exINT3{slash}SEG4-Pad13)") (class "Default")
      (node (ref "U7") (pin "13") (pinfunction "GPIO12/RXD3/exINT3/SEG4_13") (pintype "bidirectional"))
    )
    (net (code "291") (name "unconnected-(U7-GPIO13{slash}TXD3{slash}exINT4{slash}SEG5-Pad14)") (class "Default")
      (node (ref "U7") (pin "14") (pinfunction "GPIO13/TXD3/exINT4/SEG5_14") (pintype "bidirectional"))
    )
    (net (code "292") (name "unconnected-(U7-GPIO30{slash}SEG16{slash}EXOUT2{slash}P30-Pad33)") (class "Default")
      (node (ref "U7") (pin "33") (pinfunction "GPIO30/SEG16/EXOUT2/P30_33") (pintype "bidirectional"))
    )
    (net (code "293") (name "unconnected-(U7-GPIO33{slash}SEG19{slash}PCACOMP2{slash}P33-Pad36)") (class "Default")
      (node (ref "U7") (pin "36") (pinfunction "GPIO33/SEG19/PCACOMP2/P33_36") (pintype "bidirectional"))
    )
    (net (code "294") (name "unconnected-(U7-GPIO34{slash}SEG20{slash}PCACOMP3{slash}P34-Pad37)") (class "Default")
      (node (ref "U7") (pin "37") (pinfunction "GPIO34/SEG20/PCACOMP3/P34_37") (pintype "bidirectional"))
    )
    (net (code "295") (name "unconnected-(U7-GPIO44{slash}SEG23{slash}timer1-Pad49)") (class "Default")
      (node (ref "U7") (pin "49") (pinfunction "GPIO44/SEG23/timer1_49") (pintype "bidirectional"))
    )
    (net (code "296") (name "unconnected-(U7-GPIO45{slash}AN0-Pad50)") (class "Default")
      (node (ref "U7") (pin "50") (pinfunction "GPIO45/AN0_50") (pintype "bidirectional"))
    )
    (net (code "297") (name "unconnected-(U7-GPIO46{slash}SEG24{slash}AN1-Pad51)") (class "Default")
      (node (ref "U7") (pin "51") (pinfunction "GPIO46/SEG24/AN1_51") (pintype "bidirectional"))
    )
    (net (code "298") (name "unconnected-(U7-GPIO47{slash}SEG25{slash}timer0gate{slash}AN2-Pad52)") (class "Default")
      (node (ref "U7") (pin "52") (pinfunction "GPIO47/SEG25/timer0gate/AN2_52") (pintype "bidirectional"))
    )
    (net (code "299") (name "unconnected-(U7-GPIO54{slash}SEG30{slash}AN7-Pad57)") (class "Default")
      (node (ref "U7") (pin "57") (pinfunction "GPIO54/SEG30/AN7_57") (pintype "bidirectional"))
    )
    (net (code "300") (name "unconnected-(U7-GPIO55{slash}SEG31{slash}AN8-Pad58)") (class "Default")
      (node (ref "U7") (pin "58") (pinfunction "GPIO55/SEG31/AN8_58") (pintype "bidirectional"))
    )
    (net (code "301") (name "unconnected-(U7-GPIO57{slash}SEG33{slash}BUF4TST{slash}WDTOUT{slash}AN10-Pad59)") (class "Default")
      (node (ref "U7") (pin "59") (pinfunction "GPIO57/SEG33/BUF4TST/WDTOUT/AN10_59") (pintype "bidirectional"))
    )
    (net (code "302") (name "unconnected-(U7-GPIO65{slash}REMAP0{slash}TM2-Pad79)") (class "Default")
      (node (ref "U7") (pin "79") (pinfunction "GPIO65/REMAP0/TM2_79") (pintype "bidirectional"))
    )
    (net (code "303") (name "unconnected-(U7-GPIO72{slash}exINT5{slash}SEG6-Pad15)") (class "Default")
      (node (ref "U7") (pin "15") (pinfunction "GPIO72/exINT5/SEG6_15") (pintype "bidirectional"))
    )
    (net (code "304") (name "unconnected-(U7-GPIO73{slash}exINT6{slash}SEG7-Pad16)") (class "Default")
      (node (ref "U7") (pin "16") (pinfunction "GPIO73/exINT6/SEG7_16") (pintype "bidirectional"))
    )
    (net (code "305") (name "unconnected-(U7-GPIO80{slash}VDISP0{slash}P20-Pad44)") (class "Default")
      (node (ref "U7") (pin "44") (pinfunction "GPIO80/VDISP0/P20_44") (pintype "bidirectional"))
    )
    (net (code "306") (name "unconnected-(U7-GPIO81{slash}VDISP1{slash}P21-Pad45)") (class "Default")
      (node (ref "U7") (pin "45") (pinfunction "GPIO81/VDISP1/P21_45") (pintype "bidirectional"))
    )
    (net (code "307") (name "unconnected-(U7-GPIO82{slash}VDISP2{slash}P22-Pad46)") (class "Default")
      (node (ref "U7") (pin "46") (pinfunction "GPIO82/VDISP2/P22_46") (pintype "bidirectional"))
    )
    (net (code "308") (name "unconnected-(U7-GPIO83{slash}VDISP3{slash}P23-Pad47)") (class "Default")
      (node (ref "U7") (pin "47") (pinfunction "GPIO83/VDISP3/P23_47") (pintype "bidirectional"))
    )
    (net (code "309") (name "unconnected-(U7-GPIO84{slash}VCIN1{slash}P24-Pad69)") (class "Default")
      (node (ref "U7") (pin "69") (pinfunction "GPIO84/VCIN1/P24_69") (pintype "bidirectional"))
    )
    (net (code "310") (name "unconnected-(U7-GPIO85{slash}VCIN2{slash}P25-Pad70)") (class "Default")
      (node (ref "U7") (pin "70") (pinfunction "GPIO85/VCIN2/P25_70") (pintype "bidirectional"))
    )
    (net (code "311") (name "unconnected-(U7-GPIO86{slash}SEG34{slash}P26-Pad71)") (class "Default")
      (node (ref "U7") (pin "71") (pinfunction "GPIO86/SEG34/P26_71") (pintype "bidirectional"))
    )
    (net (code "312") (name "unconnected-(U7-GPIO87{slash}SEG35{slash}P27-Pad72)") (class "Default")
      (node (ref "U7") (pin "72") (pinfunction "GPIO87/SEG35/P27_72") (pintype "bidirectional"))
    )
    (net (code "313") (name "unconnected-(U7-GPIO90{slash}AN11{slash}SEG40-Pad62)") (class "Default")
      (node (ref "U7") (pin "62") (pinfunction "GPIO90/AN11/SEG40_62") (pintype "bidirectional"))
    )
    (net (code "314") (name "unconnected-(U7-VDD50-Pad65)") (class "Default")
      (node (ref "U7") (pin "65") (pinfunction "VDD50_65") (pintype "passive"))
    )
    (net (code "315") (name "unconnected-(U8-NC-Pad1)") (class "Default")
      (node (ref "U8") (pin "1") (pinfunction "NC_1") (pintype "passive+no_connect"))
    )
    (net (code "316") (name "unconnected-(U8-NC-Pad5)") (class "Default")
      (node (ref "U8") (pin "5") (pinfunction "NC_5") (pintype "passive+no_connect"))
    )
    (net (code "317") (name "unconnected-(U8-NC-Pad8)") (class "Default")
      (node (ref "U8") (pin "8") (pinfunction "NC_8") (pintype "passive+no_connect"))
    )
  )
)
